# Sensor_Gabung.net
KiCad netlist of a schematic drawn in EAGLE
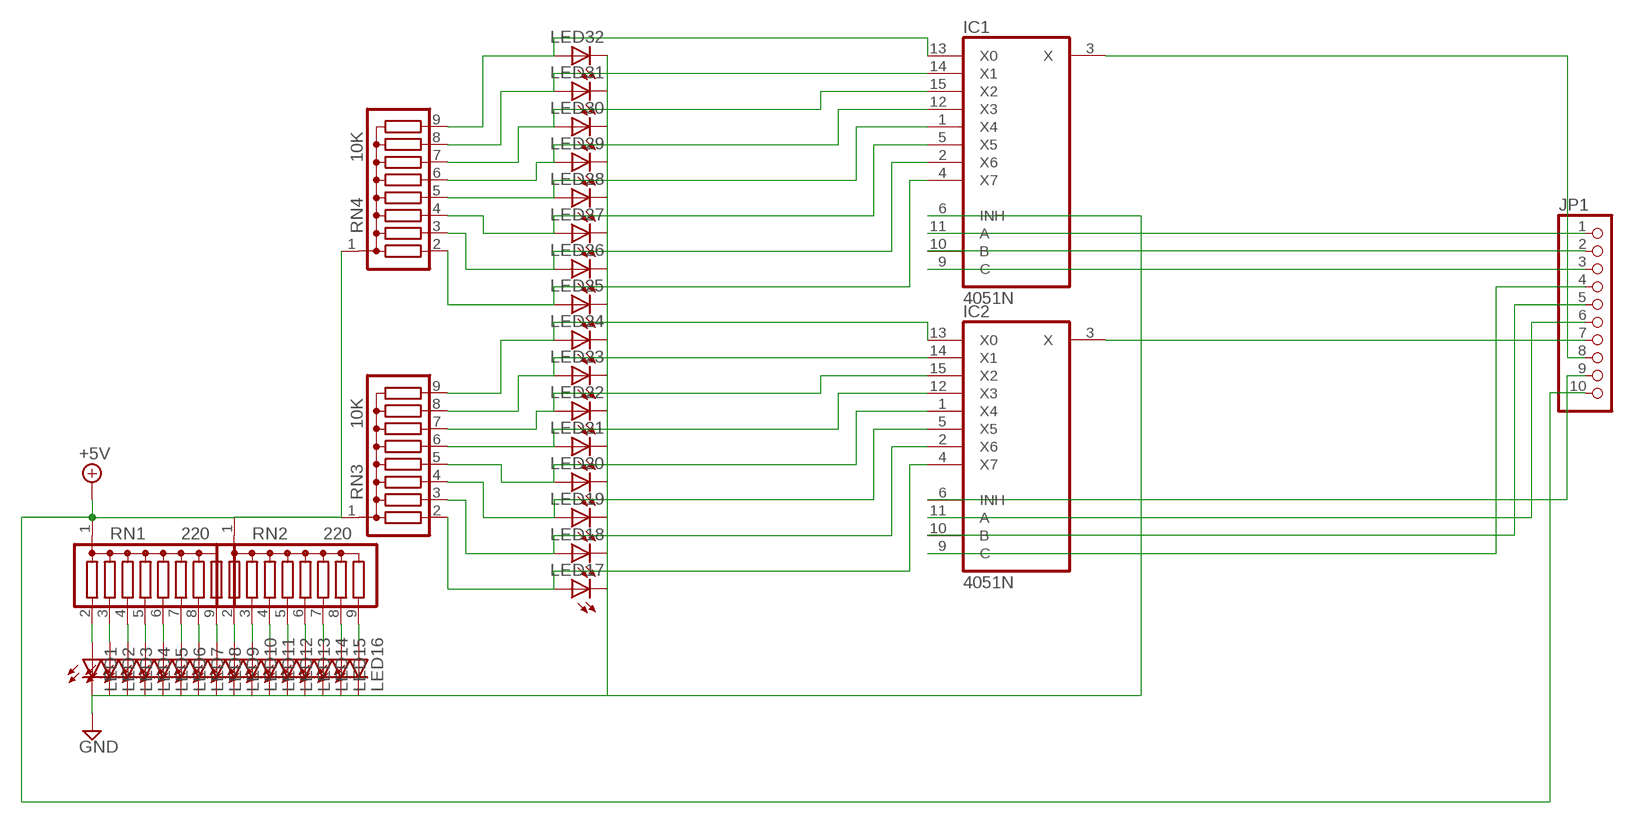
[diagram p0: schematic, sheet 1]
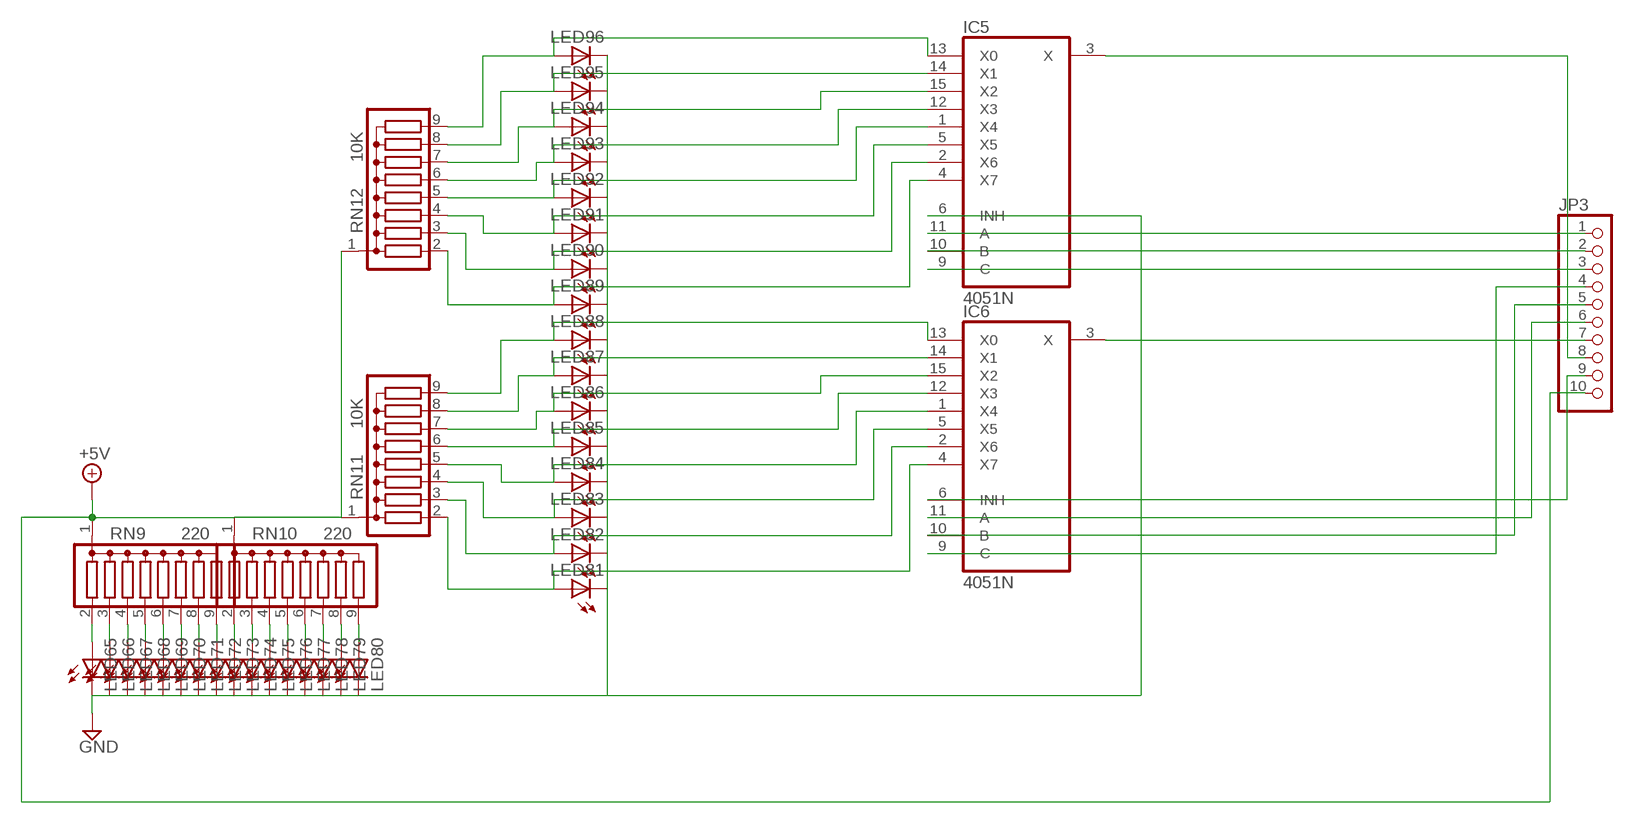
[diagram p1: schematic, sheet 2]
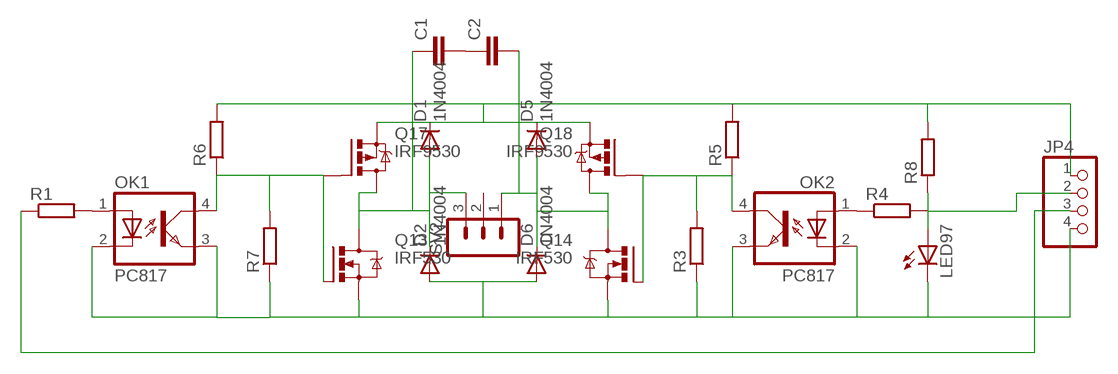
[diagram p2: schematic, sheet 3]
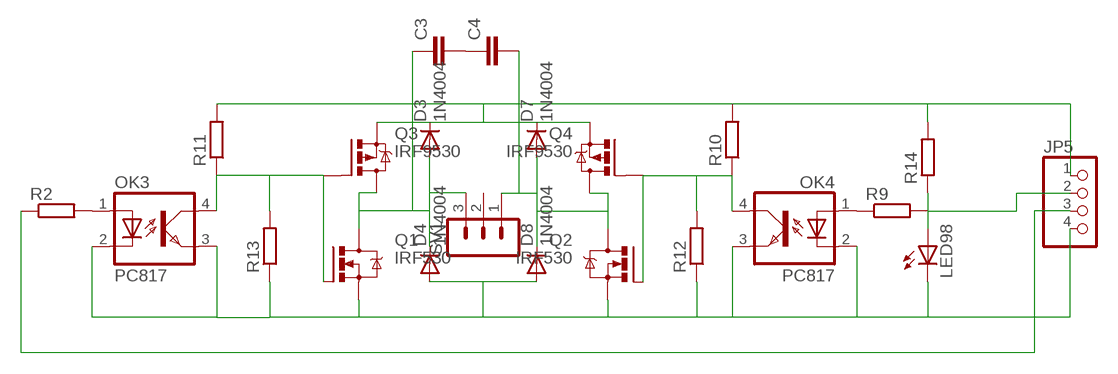
[diagram p3: schematic, sheet 4]
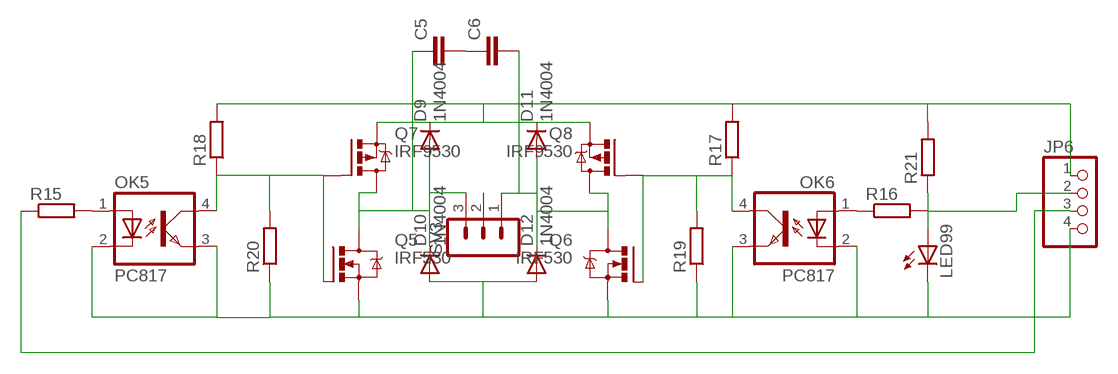
[diagram p4: schematic, sheet 5]
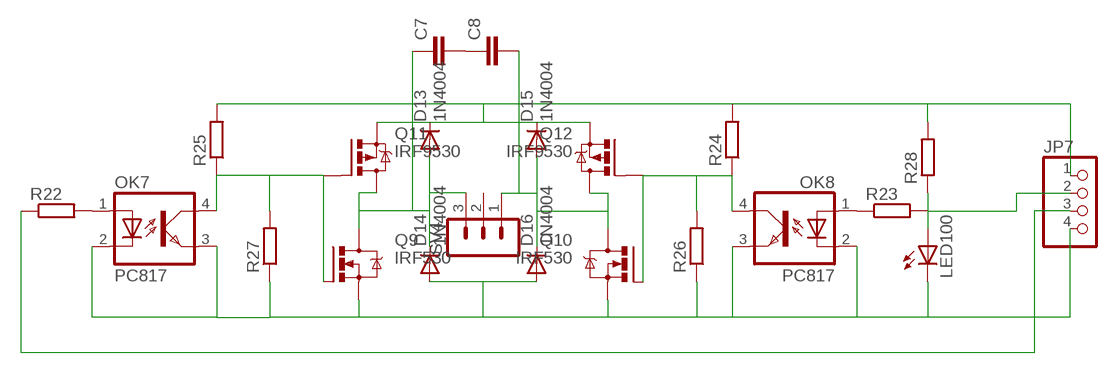
[diagram p5: schematic, sheet 6]
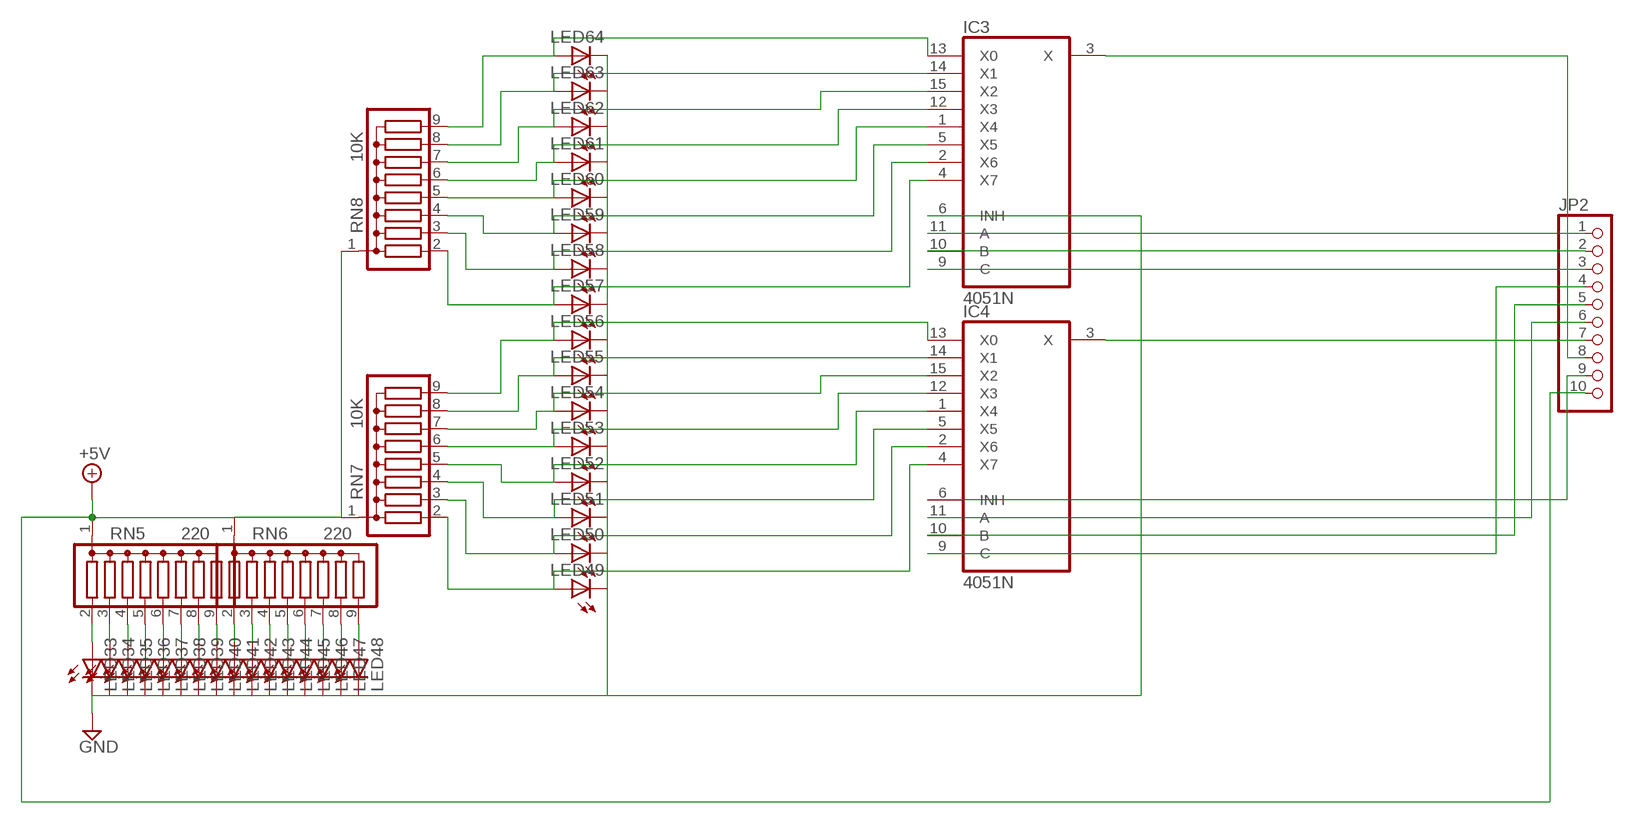
[diagram p6: schematic, sheet 7]
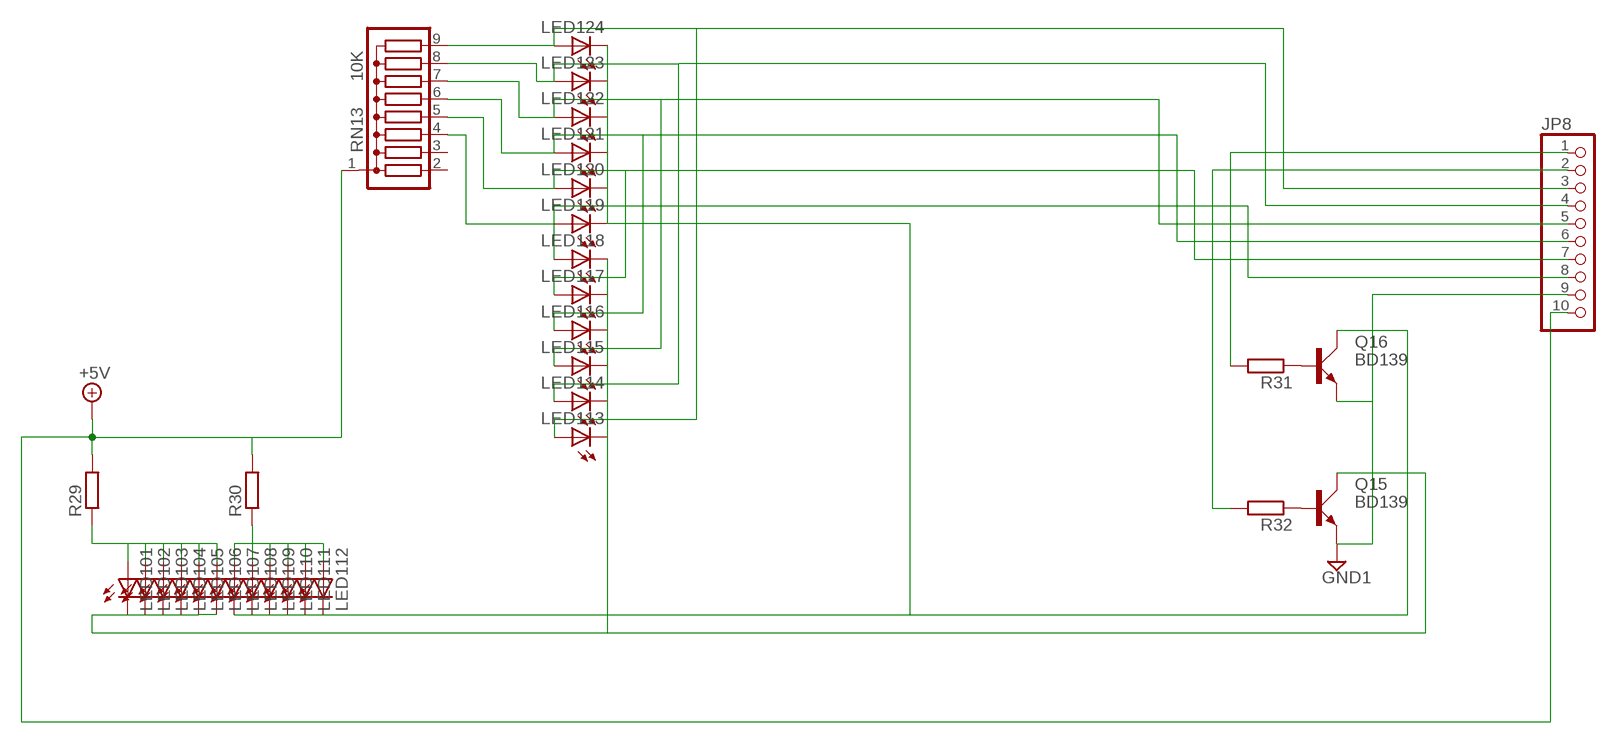
[diagram p7: schematic, sheet 8]
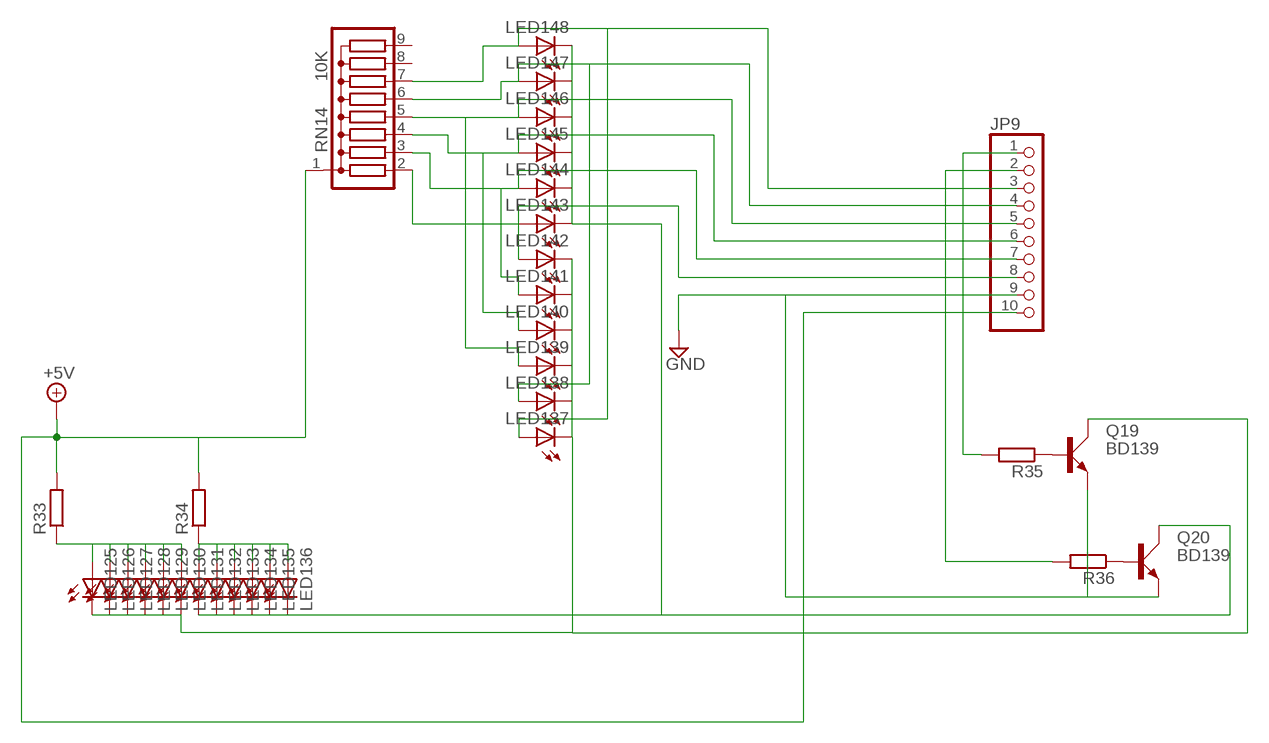
[diagram p8: schematic, sheet 9]

(export (version "E")
  (design (tool "Eeschema 10.0.6"))
  (components
    (comp (ref "JP9")
      (value "PINHD-1X10")
      (footprint "eagle-import:1X10")
      (libsource (lib "eagle-import") (part "PINHD-1X10"))
    )
    (comp (ref "LED125")
      (value "LED3MM")
      (footprint "eagle-import:LED3MM")
      (libsource (lib "eagle-import") (part "LED3MM"))
    )
    (comp (ref "LED126")
      (value "LED3MM")
      (footprint "eagle-import:LED3MM")
      (libsource (lib "eagle-import") (part "LED3MM"))
    )
    (comp (ref "LED127")
      (value "LED3MM")
      (footprint "eagle-import:LED3MM")
      (libsource (lib "eagle-import") (part "LED3MM"))
    )
    (comp (ref "LED128")
      (value "LED3MM")
      (footprint "eagle-import:LED3MM")
      (libsource (lib "eagle-import") (part "LED3MM"))
    )
    (comp (ref "LED129")
      (value "LED3MM")
      (footprint "eagle-import:LED3MM")
      (libsource (lib "eagle-import") (part "LED3MM"))
    )
    (comp (ref "LED130")
      (value "LED3MM")
      (footprint "eagle-import:LED3MM")
      (libsource (lib "eagle-import") (part "LED3MM"))
    )
    (comp (ref "LED131")
      (value "LED3MM")
      (footprint "eagle-import:LED3MM")
      (libsource (lib "eagle-import") (part "LED3MM"))
    )
    (comp (ref "LED132")
      (value "LED3MM")
      (footprint "eagle-import:LED3MM")
      (libsource (lib "eagle-import") (part "LED3MM"))
    )
    (comp (ref "LED133")
      (value "LED3MM")
      (footprint "eagle-import:LED3MM")
      (libsource (lib "eagle-import") (part "LED3MM"))
    )
    (comp (ref "LED134")
      (value "LED3MM")
      (footprint "eagle-import:LED3MM")
      (libsource (lib "eagle-import") (part "LED3MM"))
    )
    (comp (ref "LED135")
      (value "LED3MM")
      (footprint "eagle-import:LED3MM")
      (libsource (lib "eagle-import") (part "LED3MM"))
    )
    (comp (ref "LED136")
      (value "LED3MM")
      (footprint "eagle-import:LED3MM")
      (libsource (lib "eagle-import") (part "LED3MM"))
    )
    (comp (ref "LED137")
      (value "LED3MM")
      (footprint "eagle-import:LED3MM")
      (libsource (lib "eagle-import") (part "LED3MM"))
    )
    (comp (ref "LED138")
      (value "LED3MM")
      (footprint "eagle-import:LED3MM")
      (libsource (lib "eagle-import") (part "LED3MM"))
    )
    (comp (ref "LED139")
      (value "LED3MM")
      (footprint "eagle-import:LED3MM")
      (libsource (lib "eagle-import") (part "LED3MM"))
    )
    (comp (ref "LED140")
      (value "LED3MM")
      (footprint "eagle-import:LED3MM")
      (libsource (lib "eagle-import") (part "LED3MM"))
    )
    (comp (ref "LED141")
      (value "LED3MM")
      (footprint "eagle-import:LED3MM")
      (libsource (lib "eagle-import") (part "LED3MM"))
    )
    (comp (ref "LED142")
      (value "LED3MM")
      (footprint "eagle-import:LED3MM")
      (libsource (lib "eagle-import") (part "LED3MM"))
    )
    (comp (ref "LED143")
      (value "LED3MM")
      (footprint "eagle-import:LED3MM")
      (libsource (lib "eagle-import") (part "LED3MM"))
    )
    (comp (ref "LED144")
      (value "LED3MM")
      (footprint "eagle-import:LED3MM")
      (libsource (lib "eagle-import") (part "LED3MM"))
    )
    (comp (ref "LED145")
      (value "LED3MM")
      (footprint "eagle-import:LED3MM")
      (libsource (lib "eagle-import") (part "LED3MM"))
    )
    (comp (ref "LED146")
      (value "LED3MM")
      (footprint "eagle-import:LED3MM")
      (libsource (lib "eagle-import") (part "LED3MM"))
    )
    (comp (ref "LED147")
      (value "LED3MM")
      (footprint "eagle-import:LED3MM")
      (libsource (lib "eagle-import") (part "LED3MM"))
    )
    (comp (ref "LED148")
      (value "LED3MM")
      (footprint "eagle-import:LED3MM")
      (libsource (lib "eagle-import") (part "LED3MM"))
    )
    (comp (ref "Q19")
      (value "BD139")
      (footprint "eagle-import:TO126AV")
      (libsource (lib "eagle-import") (part "BD139"))
    )
    (comp (ref "Q20")
      (value "BD139")
      (footprint "eagle-import:TO126AV")
      (libsource (lib "eagle-import") (part "BD139"))
    )
    (comp (ref "R33")
      (value "R-EU_0204/7")
      (footprint "eagle-import:0204_7")
      (libsource (lib "eagle-import") (part "R-EU_0204/7"))
    )
    (comp (ref "R34")
      (value "R-EU_0204/7")
      (footprint "eagle-import:0204_7")
      (libsource (lib "eagle-import") (part "R-EU_0204/7"))
    )
    (comp (ref "R35")
      (value "R-EU_0204/7")
      (footprint "eagle-import:0204_7")
      (libsource (lib "eagle-import") (part "R-EU_0204/7"))
    )
    (comp (ref "R36")
      (value "R-EU_0204/7")
      (footprint "eagle-import:0204_7")
      (libsource (lib "eagle-import") (part "R-EU_0204/7"))
    )
    (comp (ref "RN14")
      (value "10K")
      (footprint "eagle-import:SIL9")
      (libsource (lib "eagle-import") (part "G08R"))
    )
    (comp (ref "C5")
      (value "C-EU025-025X050")
      (footprint "eagle-import:C025-025X050")
      (libsource (lib "eagle-import") (part "C-EU025-025X050"))
    )
    (comp (ref "C6")
      (value "C-EU025-025X050")
      (footprint "eagle-import:C025-025X050")
      (libsource (lib "eagle-import") (part "C-EU025-025X050"))
    )
    (comp (ref "D9")
      (value "1N4004")
      (footprint "eagle-import:DO41-10")
      (libsource (lib "eagle-import") (part "1N4004"))
    )
    (comp (ref "D10")
      (value "1N4004")
      (footprint "eagle-import:DO41-10")
      (libsource (lib "eagle-import") (part "1N4004"))
    )
    (comp (ref "D11")
      (value "1N4004")
      (footprint "eagle-import:DO41-10")
      (libsource (lib "eagle-import") (part "1N4004"))
    )
    (comp (ref "D12")
      (value "1N4004")
      (footprint "eagle-import:DO41-10")
      (libsource (lib "eagle-import") (part "1N4004"))
    )
    (comp (ref "JP6")
      (value "PINHD-1X4")
      (footprint "eagle-import:1X04")
      (libsource (lib "eagle-import") (part "PINHD-1X4"))
    )
    (comp (ref "LED99")
      (value "LED3MM")
      (footprint "eagle-import:LED3MM")
      (libsource (lib "eagle-import") (part "LED3MM"))
    )
    (comp (ref "OK5")
      (value "PC817")
      (footprint "eagle-import:DIL04")
      (fields (field (name "MPN") "PC817X4J000F"))
      (libsource (lib "eagle-import") (part "PC817"))
    )
    (comp (ref "OK6")
      (value "PC817")
      (footprint "eagle-import:DIL04")
      (fields (field (name "MPN") "PC817X4J000F"))
      (libsource (lib "eagle-import") (part "PC817"))
    )
    (comp (ref "Q5")
      (value "IRF530")
      (footprint "eagle-import:TO220BV")
      (libsource (lib "eagle-import") (part "IRF530"))
    )
    (comp (ref "Q6")
      (value "IRF530")
      (footprint "eagle-import:TO220BV")
      (libsource (lib "eagle-import") (part "IRF530"))
    )
    (comp (ref "Q7")
      (value "IRF9530")
      (footprint "eagle-import:TO220BV")
      (libsource (lib "eagle-import") (part "IRF9530"))
    )
    (comp (ref "Q8")
      (value "IRF9530")
      (footprint "eagle-import:TO220BV")
      (libsource (lib "eagle-import") (part "IRF9530"))
    )
    (comp (ref "R15")
      (value "R-EU_0207/10")
      (footprint "eagle-import:0207_10")
      (libsource (lib "eagle-import") (part "R-EU_0207/10"))
    )
    (comp (ref "R16")
      (value "R-EU_0207/10")
      (footprint "eagle-import:0207_10")
      (libsource (lib "eagle-import") (part "R-EU_0207/10"))
    )
    (comp (ref "R17")
      (value "R-EU_0207/10")
      (footprint "eagle-import:0207_10")
      (libsource (lib "eagle-import") (part "R-EU_0207/10"))
    )
    (comp (ref "R18")
      (value "R-EU_0207/10")
      (footprint "eagle-import:0207_10")
      (libsource (lib "eagle-import") (part "R-EU_0207/10"))
    )
    (comp (ref "R19")
      (value "R-EU_0204/7")
      (footprint "eagle-import:0204_7")
      (libsource (lib "eagle-import") (part "R-EU_0204/7"))
    )
    (comp (ref "R20")
      (value "R-EU_0204/7")
      (footprint "eagle-import:0204_7")
      (libsource (lib "eagle-import") (part "R-EU_0204/7"))
    )
    (comp (ref "R21")
      (value "R-EU_0207/10")
      (footprint "eagle-import:0207_10")
      (libsource (lib "eagle-import") (part "R-EU_0207/10"))
    )
    (comp (ref "SV3")
      (value "MA03-1")
      (footprint "eagle-import:MA03-1")
      (libsource (lib "eagle-import") (part "MA03-1"))
    )
    (comp (ref "C1")
      (value "C-EU025-025X050")
      (footprint "eagle-import:C025-025X050")
      (libsource (lib "eagle-import") (part "C-EU025-025X050"))
    )
    (comp (ref "C2")
      (value "C-EU025-025X050")
      (footprint "eagle-import:C025-025X050")
      (libsource (lib "eagle-import") (part "C-EU025-025X050"))
    )
    (comp (ref "D1")
      (value "1N4004")
      (footprint "eagle-import:DO41-10")
      (libsource (lib "eagle-import") (part "1N4004"))
    )
    (comp (ref "D2")
      (value "1N4004")
      (footprint "eagle-import:DO41-10")
      (libsource (lib "eagle-import") (part "1N4004"))
    )
    (comp (ref "D5")
      (value "1N4004")
      (footprint "eagle-import:DO41-10")
      (libsource (lib "eagle-import") (part "1N4004"))
    )
    (comp (ref "D6")
      (value "1N4004")
      (footprint "eagle-import:DO41-10")
      (libsource (lib "eagle-import") (part "1N4004"))
    )
    (comp (ref "JP4")
      (value "PINHD-1X4")
      (footprint "eagle-import:1X04")
      (libsource (lib "eagle-import") (part "PINHD-1X4"))
    )
    (comp (ref "LED97")
      (value "LED3MM")
      (footprint "eagle-import:LED3MM")
      (libsource (lib "eagle-import") (part "LED3MM"))
    )
    (comp (ref "OK1")
      (value "PC817")
      (footprint "eagle-import:DIL04")
      (fields (field (name "MPN") "PC817X4J000F"))
      (libsource (lib "eagle-import") (part "PC817"))
    )
    (comp (ref "OK2")
      (value "PC817")
      (footprint "eagle-import:DIL04")
      (fields (field (name "MPN") "PC817X4J000F"))
      (libsource (lib "eagle-import") (part "PC817"))
    )
    (comp (ref "Q13")
      (value "IRF530")
      (footprint "eagle-import:TO220BV")
      (libsource (lib "eagle-import") (part "IRF530"))
    )
    (comp (ref "Q14")
      (value "IRF530")
      (footprint "eagle-import:TO220BV")
      (libsource (lib "eagle-import") (part "IRF530"))
    )
    (comp (ref "Q17")
      (value "IRF9530")
      (footprint "eagle-import:TO220BV")
      (libsource (lib "eagle-import") (part "IRF9530"))
    )
    (comp (ref "Q18")
      (value "IRF9530")
      (footprint "eagle-import:TO220BV")
      (libsource (lib "eagle-import") (part "IRF9530"))
    )
    (comp (ref "R1")
      (value "R-EU_0207/10")
      (footprint "eagle-import:0207_10")
      (libsource (lib "eagle-import") (part "R-EU_0207/10"))
    )
    (comp (ref "R3")
      (value "R-EU_0204/7")
      (footprint "eagle-import:0204_7")
      (libsource (lib "eagle-import") (part "R-EU_0204/7"))
    )
    (comp (ref "R4")
      (value "R-EU_0207/10")
      (footprint "eagle-import:0207_10")
      (libsource (lib "eagle-import") (part "R-EU_0207/10"))
    )
    (comp (ref "R5")
      (value "R-EU_0207/10")
      (footprint "eagle-import:0207_10")
      (libsource (lib "eagle-import") (part "R-EU_0207/10"))
    )
    (comp (ref "R6")
      (value "R-EU_0207/10")
      (footprint "eagle-import:0207_10")
      (libsource (lib "eagle-import") (part "R-EU_0207/10"))
    )
    (comp (ref "R7")
      (value "R-EU_0204/7")
      (footprint "eagle-import:0204_7")
      (libsource (lib "eagle-import") (part "R-EU_0204/7"))
    )
    (comp (ref "R8")
      (value "R-EU_0207/10")
      (footprint "eagle-import:0207_10")
      (libsource (lib "eagle-import") (part "R-EU_0207/10"))
    )
    (comp (ref "SV2")
      (value "MA03-1")
      (footprint "eagle-import:MA03-1")
      (libsource (lib "eagle-import") (part "MA03-1"))
    )
    (comp (ref "C3")
      (value "C-EU025-025X050")
      (footprint "eagle-import:C025-025X050")
      (libsource (lib "eagle-import") (part "C-EU025-025X050"))
    )
    (comp (ref "C4")
      (value "C-EU025-025X050")
      (footprint "eagle-import:C025-025X050")
      (libsource (lib "eagle-import") (part "C-EU025-025X050"))
    )
    (comp (ref "D3")
      (value "1N4004")
      (footprint "eagle-import:DO41-10")
      (libsource (lib "eagle-import") (part "1N4004"))
    )
    (comp (ref "D4")
      (value "1N4004")
      (footprint "eagle-import:DO41-10")
      (libsource (lib "eagle-import") (part "1N4004"))
    )
    (comp (ref "D7")
      (value "1N4004")
      (footprint "eagle-import:DO41-10")
      (libsource (lib "eagle-import") (part "1N4004"))
    )
    (comp (ref "D8")
      (value "1N4004")
      (footprint "eagle-import:DO41-10")
      (libsource (lib "eagle-import") (part "1N4004"))
    )
    (comp (ref "JP5")
      (value "PINHD-1X4")
      (footprint "eagle-import:1X04")
      (libsource (lib "eagle-import") (part "PINHD-1X4"))
    )
    (comp (ref "LED98")
      (value "LED3MM")
      (footprint "eagle-import:LED3MM")
      (libsource (lib "eagle-import") (part "LED3MM"))
    )
    (comp (ref "OK3")
      (value "PC817")
      (footprint "eagle-import:DIL04")
      (fields (field (name "MPN") "PC817X4J000F"))
      (libsource (lib "eagle-import") (part "PC817"))
    )
    (comp (ref "OK4")
      (value "PC817")
      (footprint "eagle-import:DIL04")
      (fields (field (name "MPN") "PC817X4J000F"))
      (libsource (lib "eagle-import") (part "PC817"))
    )
    (comp (ref "Q1")
      (value "IRF530")
      (footprint "eagle-import:TO220BV")
      (libsource (lib "eagle-import") (part "IRF530"))
    )
    (comp (ref "Q2")
      (value "IRF530")
      (footprint "eagle-import:TO220BV")
      (libsource (lib "eagle-import") (part "IRF530"))
    )
    (comp (ref "Q3")
      (value "IRF9530")
      (footprint "eagle-import:TO220BV")
      (libsource (lib "eagle-import") (part "IRF9530"))
    )
    (comp (ref "Q4")
      (value "IRF9530")
      (footprint "eagle-import:TO220BV")
      (libsource (lib "eagle-import") (part "IRF9530"))
    )
    (comp (ref "R2")
      (value "R-EU_0207/10")
      (footprint "eagle-import:0207_10")
      (libsource (lib "eagle-import") (part "R-EU_0207/10"))
    )
    (comp (ref "R9")
      (value "R-EU_0207/10")
      (footprint "eagle-import:0207_10")
      (libsource (lib "eagle-import") (part "R-EU_0207/10"))
    )
    (comp (ref "R10")
      (value "R-EU_0207/10")
      (footprint "eagle-import:0207_10")
      (libsource (lib "eagle-import") (part "R-EU_0207/10"))
    )
    (comp (ref "R11")
      (value "R-EU_0207/10")
      (footprint "eagle-import:0207_10")
      (libsource (lib "eagle-import") (part "R-EU_0207/10"))
    )
    (comp (ref "R12")
      (value "R-EU_0204/7")
      (footprint "eagle-import:0204_7")
      (libsource (lib "eagle-import") (part "R-EU_0204/7"))
    )
    (comp (ref "R13")
      (value "R-EU_0204/7")
      (footprint "eagle-import:0204_7")
      (libsource (lib "eagle-import") (part "R-EU_0204/7"))
    )
    (comp (ref "R14")
      (value "R-EU_0207/10")
      (footprint "eagle-import:0207_10")
      (libsource (lib "eagle-import") (part "R-EU_0207/10"))
    )
    (comp (ref "SV1")
      (value "MA03-1")
      (footprint "eagle-import:MA03-1")
      (libsource (lib "eagle-import") (part "MA03-1"))
    )
    (comp (ref "JP8")
      (value "PINHD-1X10")
      (footprint "eagle-import:1X10")
      (libsource (lib "eagle-import") (part "PINHD-1X10"))
    )
    (comp (ref "LED101")
      (value "LED3MM")
      (footprint "eagle-import:LED3MM")
      (libsource (lib "eagle-import") (part "LED3MM"))
    )
    (comp (ref "LED102")
      (value "LED3MM")
      (footprint "eagle-import:LED3MM")
      (libsource (lib "eagle-import") (part "LED3MM"))
    )
    (comp (ref "LED103")
      (value "LED3MM")
      (footprint "eagle-import:LED3MM")
      (libsource (lib "eagle-import") (part "LED3MM"))
    )
    (comp (ref "LED104")
      (value "LED3MM")
      (footprint "eagle-import:LED3MM")
      (libsource (lib "eagle-import") (part "LED3MM"))
    )
    (comp (ref "LED105")
      (value "LED3MM")
      (footprint "eagle-import:LED3MM")
      (libsource (lib "eagle-import") (part "LED3MM"))
    )
    (comp (ref "LED106")
      (value "LED3MM")
      (footprint "eagle-import:LED3MM")
      (libsource (lib "eagle-import") (part "LED3MM"))
    )
    (comp (ref "LED107")
      (value "LED3MM")
      (footprint "eagle-import:LED3MM")
      (libsource (lib "eagle-import") (part "LED3MM"))
    )
    (comp (ref "LED108")
      (value "LED3MM")
      (footprint "eagle-import:LED3MM")
      (libsource (lib "eagle-import") (part "LED3MM"))
    )
    (comp (ref "LED109")
      (value "LED3MM")
      (footprint "eagle-import:LED3MM")
      (libsource (lib "eagle-import") (part "LED3MM"))
    )
    (comp (ref "LED110")
      (value "LED3MM")
      (footprint "eagle-import:LED3MM")
      (libsource (lib "eagle-import") (part "LED3MM"))
    )
    (comp (ref "LED111")
      (value "LED3MM")
      (footprint "eagle-import:LED3MM")
      (libsource (lib "eagle-import") (part "LED3MM"))
    )
    (comp (ref "LED112")
      (value "LED3MM")
      (footprint "eagle-import:LED3MM")
      (libsource (lib "eagle-import") (part "LED3MM"))
    )
    (comp (ref "LED113")
      (value "LED3MM")
      (footprint "eagle-import:LED3MM")
      (libsource (lib "eagle-import") (part "LED3MM"))
    )
    (comp (ref "LED114")
      (value "LED3MM")
      (footprint "eagle-import:LED3MM")
      (libsource (lib "eagle-import") (part "LED3MM"))
    )
    (comp (ref "LED115")
      (value "LED3MM")
      (footprint "eagle-import:LED3MM")
      (libsource (lib "eagle-import") (part "LED3MM"))
    )
    (comp (ref "LED116")
      (value "LED3MM")
      (footprint "eagle-import:LED3MM")
      (libsource (lib "eagle-import") (part "LED3MM"))
    )
    (comp (ref "LED117")
      (value "LED3MM")
      (footprint "eagle-import:LED3MM")
      (libsource (lib "eagle-import") (part "LED3MM"))
    )
    (comp (ref "LED118")
      (value "LED3MM")
      (footprint "eagle-import:LED3MM")
      (libsource (lib "eagle-import") (part "LED3MM"))
    )
    (comp (ref "LED119")
      (value "LED3MM")
      (footprint "eagle-import:LED3MM")
      (libsource (lib "eagle-import") (part "LED3MM"))
    )
    (comp (ref "LED120")
      (value "LED3MM")
      (footprint "eagle-import:LED3MM")
      (libsource (lib "eagle-import") (part "LED3MM"))
    )
    (comp (ref "LED121")
      (value "LED3MM")
      (footprint "eagle-import:LED3MM")
      (libsource (lib "eagle-import") (part "LED3MM"))
    )
    (comp (ref "LED122")
      (value "LED3MM")
      (footprint "eagle-import:LED3MM")
      (libsource (lib "eagle-import") (part "LED3MM"))
    )
    (comp (ref "LED123")
      (value "LED3MM")
      (footprint "eagle-import:LED3MM")
      (libsource (lib "eagle-import") (part "LED3MM"))
    )
    (comp (ref "LED124")
      (value "LED3MM")
      (footprint "eagle-import:LED3MM")
      (libsource (lib "eagle-import") (part "LED3MM"))
    )
    (comp (ref "Q15")
      (value "BD139")
      (footprint "eagle-import:TO126AV")
      (libsource (lib "eagle-import") (part "BD139"))
    )
    (comp (ref "Q16")
      (value "BD139")
      (footprint "eagle-import:TO126AV")
      (libsource (lib "eagle-import") (part "BD139"))
    )
    (comp (ref "R29")
      (value "R-EU_0207/10")
      (footprint "eagle-import:0207_10")
      (libsource (lib "eagle-import") (part "R-EU_0207/10"))
    )
    (comp (ref "R30")
      (value "R-EU_0207/10")
      (footprint "eagle-import:0207_10")
      (libsource (lib "eagle-import") (part "R-EU_0207/10"))
    )
    (comp (ref "R31")
      (value "R-EU_0207/10")
      (footprint "eagle-import:0207_10")
      (libsource (lib "eagle-import") (part "R-EU_0207/10"))
    )
    (comp (ref "R32")
      (value "R-EU_0207/10")
      (footprint "eagle-import:0207_10")
      (libsource (lib "eagle-import") (part "R-EU_0207/10"))
    )
    (comp (ref "RN13")
      (value "10K")
      (footprint "eagle-import:SIL9")
      (libsource (lib "eagle-import") (part "G08R"))
    )
    (comp (ref "C7")
      (value "C-EU025-025X050")
      (footprint "eagle-import:C025-025X050")
      (libsource (lib "eagle-import") (part "C-EU025-025X050"))
    )
    (comp (ref "C8")
      (value "C-EU025-025X050")
      (footprint "eagle-import:C025-025X050")
      (libsource (lib "eagle-import") (part "C-EU025-025X050"))
    )
    (comp (ref "D13")
      (value "1N4004")
      (footprint "eagle-import:DO41-10")
      (libsource (lib "eagle-import") (part "1N4004"))
    )
    (comp (ref "D14")
      (value "1N4004")
      (footprint "eagle-import:DO41-10")
      (libsource (lib "eagle-import") (part "1N4004"))
    )
    (comp (ref "D15")
      (value "1N4004")
      (footprint "eagle-import:DO41-10")
      (libsource (lib "eagle-import") (part "1N4004"))
    )
    (comp (ref "D16")
      (value "1N4004")
      (footprint "eagle-import:DO41-10")
      (libsource (lib "eagle-import") (part "1N4004"))
    )
    (comp (ref "JP7")
      (value "PINHD-1X4")
      (footprint "eagle-import:1X04")
      (libsource (lib "eagle-import") (part "PINHD-1X4"))
    )
    (comp (ref "LED100")
      (value "LED3MM")
      (footprint "eagle-import:LED3MM")
      (libsource (lib "eagle-import") (part "LED3MM"))
    )
    (comp (ref "OK7")
      (value "PC817")
      (footprint "eagle-import:DIL04")
      (fields (field (name "MPN") "PC817X4J000F"))
      (libsource (lib "eagle-import") (part "PC817"))
    )
    (comp (ref "OK8")
      (value "PC817")
      (footprint "eagle-import:DIL04")
      (fields (field (name "MPN") "PC817X4J000F"))
      (libsource (lib "eagle-import") (part "PC817"))
    )
    (comp (ref "Q9")
      (value "IRF530")
      (footprint "eagle-import:TO220BV")
      (libsource (lib "eagle-import") (part "IRF530"))
    )
    (comp (ref "Q10")
      (value "IRF530")
      (footprint "eagle-import:TO220BV")
      (libsource (lib "eagle-import") (part "IRF530"))
    )
    (comp (ref "Q11")
      (value "IRF9530")
      (footprint "eagle-import:TO220BV")
      (libsource (lib "eagle-import") (part "IRF9530"))
    )
    (comp (ref "Q12")
      (value "IRF9530")
      (footprint "eagle-import:TO220BV")
      (libsource (lib "eagle-import") (part "IRF9530"))
    )
    (comp (ref "R22")
      (value "R-EU_0207/10")
      (footprint "eagle-import:0207_10")
      (libsource (lib "eagle-import") (part "R-EU_0207/10"))
    )
    (comp (ref "R23")
      (value "R-EU_0207/10")
      (footprint "eagle-import:0207_10")
      (libsource (lib "eagle-import") (part "R-EU_0207/10"))
    )
    (comp (ref "R24")
      (value "R-EU_0207/10")
      (footprint "eagle-import:0207_10")
      (libsource (lib "eagle-import") (part "R-EU_0207/10"))
    )
    (comp (ref "R25")
      (value "R-EU_0207/10")
      (footprint "eagle-import:0207_10")
      (libsource (lib "eagle-import") (part "R-EU_0207/10"))
    )
    (comp (ref "R26")
      (value "R-EU_0204/7")
      (footprint "eagle-import:0204_7")
      (libsource (lib "eagle-import") (part "R-EU_0204/7"))
    )
    (comp (ref "R27")
      (value "R-EU_0204/7")
      (footprint "eagle-import:0204_7")
      (libsource (lib "eagle-import") (part "R-EU_0204/7"))
    )
    (comp (ref "R28")
      (value "R-EU_0207/10")
      (footprint "eagle-import:0207_10")
      (libsource (lib "eagle-import") (part "R-EU_0207/10"))
    )
    (comp (ref "SV4")
      (value "MA03-1")
      (footprint "eagle-import:MA03-1")
      (libsource (lib "eagle-import") (part "MA03-1"))
    )
    (comp (ref "IC3")
      (value "4051N")
      (footprint "eagle-import:DIL16")
      (libsource (lib "eagle-import") (part "4051N"))
    )
    (comp (ref "IC4")
      (value "4051N")
      (footprint "eagle-import:DIL16")
      (libsource (lib "eagle-import") (part "4051N"))
    )
    (comp (ref "JP2")
      (value "PINHD-1X10")
      (footprint "eagle-import:1X10")
      (libsource (lib "eagle-import") (part "PINHD-1X10"))
    )
    (comp (ref "LED33")
      (value "LED3MM")
      (footprint "eagle-import:LED3MM")
      (libsource (lib "eagle-import") (part "LED3MM"))
    )
    (comp (ref "LED34")
      (value "LED3MM")
      (footprint "eagle-import:LED3MM")
      (libsource (lib "eagle-import") (part "LED3MM"))
    )
    (comp (ref "LED35")
      (value "LED3MM")
      (footprint "eagle-import:LED3MM")
      (libsource (lib "eagle-import") (part "LED3MM"))
    )
    (comp (ref "LED36")
      (value "LED3MM")
      (footprint "eagle-import:LED3MM")
      (libsource (lib "eagle-import") (part "LED3MM"))
    )
    (comp (ref "LED37")
      (value "LED3MM")
      (footprint "eagle-import:LED3MM")
      (libsource (lib "eagle-import") (part "LED3MM"))
    )
    (comp (ref "LED38")
      (value "LED3MM")
      (footprint "eagle-import:LED3MM")
      (libsource (lib "eagle-import") (part "LED3MM"))
    )
    (comp (ref "LED39")
      (value "LED3MM")
      (footprint "eagle-import:LED3MM")
      (libsource (lib "eagle-import") (part "LED3MM"))
    )
    (comp (ref "LED40")
      (value "LED3MM")
      (footprint "eagle-import:LED3MM")
      (libsource (lib "eagle-import") (part "LED3MM"))
    )
    (comp (ref "LED41")
      (value "LED3MM")
      (footprint "eagle-import:LED3MM")
      (libsource (lib "eagle-import") (part "LED3MM"))
    )
    (comp (ref "LED42")
      (value "LED3MM")
      (footprint "eagle-import:LED3MM")
      (libsource (lib "eagle-import") (part "LED3MM"))
    )
    (comp (ref "LED43")
      (value "LED3MM")
      (footprint "eagle-import:LED3MM")
      (libsource (lib "eagle-import") (part "LED3MM"))
    )
    (comp (ref "LED44")
      (value "LED3MM")
      (footprint "eagle-import:LED3MM")
      (libsource (lib "eagle-import") (part "LED3MM"))
    )
    (comp (ref "LED45")
      (value "LED3MM")
      (footprint "eagle-import:LED3MM")
      (libsource (lib "eagle-import") (part "LED3MM"))
    )
    (comp (ref "LED46")
      (value "LED3MM")
      (footprint "eagle-import:LED3MM")
      (libsource (lib "eagle-import") (part "LED3MM"))
    )
    (comp (ref "LED47")
      (value "LED3MM")
      (footprint "eagle-import:LED3MM")
      (libsource (lib "eagle-import") (part "LED3MM"))
    )
    (comp (ref "LED48")
      (value "LED3MM")
      (footprint "eagle-import:LED3MM")
      (libsource (lib "eagle-import") (part "LED3MM"))
    )
    (comp (ref "LED49")
      (value "LED3MM")
      (footprint "eagle-import:LED3MM")
      (libsource (lib "eagle-import") (part "LED3MM"))
    )
    (comp (ref "LED50")
      (value "LED3MM")
      (footprint "eagle-import:LED3MM")
      (libsource (lib "eagle-import") (part "LED3MM"))
    )
    (comp (ref "LED51")
      (value "LED3MM")
      (footprint "eagle-import:LED3MM")
      (libsource (lib "eagle-import") (part "LED3MM"))
    )
    (comp (ref "LED52")
      (value "LED3MM")
      (footprint "eagle-import:LED3MM")
      (libsource (lib "eagle-import") (part "LED3MM"))
    )
    (comp (ref "LED53")
      (value "LED3MM")
      (footprint "eagle-import:LED3MM")
      (libsource (lib "eagle-import") (part "LED3MM"))
    )
    (comp (ref "LED54")
      (value "LED3MM")
      (footprint "eagle-import:LED3MM")
      (libsource (lib "eagle-import") (part "LED3MM"))
    )
    (comp (ref "LED55")
      (value "LED3MM")
      (footprint "eagle-import:LED3MM")
      (libsource (lib "eagle-import") (part "LED3MM"))
    )
    (comp (ref "LED56")
      (value "LED3MM")
      (footprint "eagle-import:LED3MM")
      (libsource (lib "eagle-import") (part "LED3MM"))
    )
    (comp (ref "LED57")
      (value "LED3MM")
      (footprint "eagle-import:LED3MM")
      (libsource (lib "eagle-import") (part "LED3MM"))
    )
    (comp (ref "LED58")
      (value "LED3MM")
      (footprint "eagle-import:LED3MM")
      (libsource (lib "eagle-import") (part "LED3MM"))
    )
    (comp (ref "LED59")
      (value "LED3MM")
      (footprint "eagle-import:LED3MM")
      (libsource (lib "eagle-import") (part "LED3MM"))
    )
    (comp (ref "LED60")
      (value "LED3MM")
      (footprint "eagle-import:LED3MM")
      (libsource (lib "eagle-import") (part "LED3MM"))
    )
    (comp (ref "LED61")
      (value "LED3MM")
      (footprint "eagle-import:LED3MM")
      (libsource (lib "eagle-import") (part "LED3MM"))
    )
    (comp (ref "LED62")
      (value "LED3MM")
      (footprint "eagle-import:LED3MM")
      (libsource (lib "eagle-import") (part "LED3MM"))
    )
    (comp (ref "LED63")
      (value "LED3MM")
      (footprint "eagle-import:LED3MM")
      (libsource (lib "eagle-import") (part "LED3MM"))
    )
    (comp (ref "LED64")
      (value "LED3MM")
      (footprint "eagle-import:LED3MM")
      (libsource (lib "eagle-import") (part "LED3MM"))
    )
    (comp (ref "RN5")
      (value "220")
      (footprint "eagle-import:SIL9")
      (libsource (lib "eagle-import") (part "G08R"))
    )
    (comp (ref "RN6")
      (value "220")
      (footprint "eagle-import:SIL9")
      (libsource (lib "eagle-import") (part "G08R"))
    )
    (comp (ref "RN7")
      (value "10K")
      (footprint "eagle-import:SIL9")
      (libsource (lib "eagle-import") (part "G08R"))
    )
    (comp (ref "RN8")
      (value "10K")
      (footprint "eagle-import:SIL9")
      (libsource (lib "eagle-import") (part "G08R"))
    )
    (comp (ref "IC1")
      (value "4051N")
      (footprint "eagle-import:DIL16")
      (libsource (lib "eagle-import") (part "4051N"))
    )
    (comp (ref "IC2")
      (value "4051N")
      (footprint "eagle-import:DIL16")
      (libsource (lib "eagle-import") (part "4051N"))
    )
    (comp (ref "JP1")
      (value "PINHD-1X10")
      (footprint "eagle-import:1X10")
      (libsource (lib "eagle-import") (part "PINHD-1X10"))
    )
    (comp (ref "LED1")
      (value "LED3MM")
      (footprint "eagle-import:LED3MM")
      (libsource (lib "eagle-import") (part "LED3MM"))
    )
    (comp (ref "LED2")
      (value "LED3MM")
      (footprint "eagle-import:LED3MM")
      (libsource (lib "eagle-import") (part "LED3MM"))
    )
    (comp (ref "LED3")
      (value "LED3MM")
      (footprint "eagle-import:LED3MM")
      (libsource (lib "eagle-import") (part "LED3MM"))
    )
    (comp (ref "LED4")
      (value "LED3MM")
      (footprint "eagle-import:LED3MM")
      (libsource (lib "eagle-import") (part "LED3MM"))
    )
    (comp (ref "LED5")
      (value "LED3MM")
      (footprint "eagle-import:LED3MM")
      (libsource (lib "eagle-import") (part "LED3MM"))
    )
    (comp (ref "LED6")
      (value "LED3MM")
      (footprint "eagle-import:LED3MM")
      (libsource (lib "eagle-import") (part "LED3MM"))
    )
    (comp (ref "LED7")
      (value "LED3MM")
      (footprint "eagle-import:LED3MM")
      (libsource (lib "eagle-import") (part "LED3MM"))
    )
    (comp (ref "LED8")
      (value "LED3MM")
      (footprint "eagle-import:LED3MM")
      (libsource (lib "eagle-import") (part "LED3MM"))
    )
    (comp (ref "LED9")
      (value "LED3MM")
      (footprint "eagle-import:LED3MM")
      (libsource (lib "eagle-import") (part "LED3MM"))
    )
    (comp (ref "LED10")
      (value "LED3MM")
      (footprint "eagle-import:LED3MM")
      (libsource (lib "eagle-import") (part "LED3MM"))
    )
    (comp (ref "LED11")
      (value "LED3MM")
      (footprint "eagle-import:LED3MM")
      (libsource (lib "eagle-import") (part "LED3MM"))
    )
    (comp (ref "LED12")
      (value "LED3MM")
      (footprint "eagle-import:LED3MM")
      (libsource (lib "eagle-import") (part "LED3MM"))
    )
    (comp (ref "LED13")
      (value "LED3MM")
      (footprint "eagle-import:LED3MM")
      (libsource (lib "eagle-import") (part "LED3MM"))
    )
    (comp (ref "LED14")
      (value "LED3MM")
      (footprint "eagle-import:LED3MM")
      (libsource (lib "eagle-import") (part "LED3MM"))
    )
    (comp (ref "LED15")
      (value "LED3MM")
      (footprint "eagle-import:LED3MM")
      (libsource (lib "eagle-import") (part "LED3MM"))
    )
    (comp (ref "LED16")
      (value "LED3MM")
      (footprint "eagle-import:LED3MM")
      (libsource (lib "eagle-import") (part "LED3MM"))
    )
    (comp (ref "LED17")
      (value "LED3MM")
      (footprint "eagle-import:LED3MM")
      (libsource (lib "eagle-import") (part "LED3MM"))
    )
    (comp (ref "LED18")
      (value "LED3MM")
      (footprint "eagle-import:LED3MM")
      (libsource (lib "eagle-import") (part "LED3MM"))
    )
    (comp (ref "LED19")
      (value "LED3MM")
      (footprint "eagle-import:LED3MM")
      (libsource (lib "eagle-import") (part "LED3MM"))
    )
    (comp (ref "LED20")
      (value "LED3MM")
      (footprint "eagle-import:LED3MM")
      (libsource (lib "eagle-import") (part "LED3MM"))
    )
    (comp (ref "LED21")
      (value "LED3MM")
      (footprint "eagle-import:LED3MM")
      (libsource (lib "eagle-import") (part "LED3MM"))
    )
    (comp (ref "LED22")
      (value "LED3MM")
      (footprint "eagle-import:LED3MM")
      (libsource (lib "eagle-import") (part "LED3MM"))
    )
    (comp (ref "LED23")
      (value "LED3MM")
      (footprint "eagle-import:LED3MM")
      (libsource (lib "eagle-import") (part "LED3MM"))
    )
    (comp (ref "LED24")
      (value "LED3MM")
      (footprint "eagle-import:LED3MM")
      (libsource (lib "eagle-import") (part "LED3MM"))
    )
    (comp (ref "LED25")
      (value "LED3MM")
      (footprint "eagle-import:LED3MM")
      (libsource (lib "eagle-import") (part "LED3MM"))
    )
    (comp (ref "LED26")
      (value "LED3MM")
      (footprint "eagle-import:LED3MM")
      (libsource (lib "eagle-import") (part "LED3MM"))
    )
    (comp (ref "LED27")
      (value "LED3MM")
      (footprint "eagle-import:LED3MM")
      (libsource (lib "eagle-import") (part "LED3MM"))
    )
    (comp (ref "LED28")
      (value "LED3MM")
      (footprint "eagle-import:LED3MM")
      (libsource (lib "eagle-import") (part "LED3MM"))
    )
    (comp (ref "LED29")
      (value "LED3MM")
      (footprint "eagle-import:LED3MM")
      (libsource (lib "eagle-import") (part "LED3MM"))
    )
    (comp (ref "LED30")
      (value "LED3MM")
      (footprint "eagle-import:LED3MM")
      (libsource (lib "eagle-import") (part "LED3MM"))
    )
    (comp (ref "LED31")
      (value "LED3MM")
      (footprint "eagle-import:LED3MM")
      (libsource (lib "eagle-import") (part "LED3MM"))
    )
    (comp (ref "LED32")
      (value "LED3MM")
      (footprint "eagle-import:LED3MM")
      (libsource (lib "eagle-import") (part "LED3MM"))
    )
    (comp (ref "RN1")
      (value "220")
      (footprint "eagle-import:SIL9")
      (libsource (lib "eagle-import") (part "G08R"))
    )
    (comp (ref "RN2")
      (value "220")
      (footprint "eagle-import:SIL9")
      (libsource (lib "eagle-import") (part "G08R"))
    )
    (comp (ref "RN3")
      (value "10K")
      (footprint "eagle-import:SIL9")
      (libsource (lib "eagle-import") (part "G08R"))
    )
    (comp (ref "RN4")
      (value "10K")
      (footprint "eagle-import:SIL9")
      (libsource (lib "eagle-import") (part "G08R"))
    )
    (comp (ref "IC5")
      (value "4051N")
      (footprint "eagle-import:DIL16")
      (libsource (lib "eagle-import") (part "4051N"))
    )
    (comp (ref "IC6")
      (value "4051N")
      (footprint "eagle-import:DIL16")
      (libsource (lib "eagle-import") (part "4051N"))
    )
    (comp (ref "JP3")
      (value "PINHD-1X10")
      (footprint "eagle-import:1X10")
      (libsource (lib "eagle-import") (part "PINHD-1X10"))
    )
    (comp (ref "LED65")
      (value "LED3MM")
      (footprint "eagle-import:LED3MM")
      (libsource (lib "eagle-import") (part "LED3MM"))
    )
    (comp (ref "LED66")
      (value "LED3MM")
      (footprint "eagle-import:LED3MM")
      (libsource (lib "eagle-import") (part "LED3MM"))
    )
    (comp (ref "LED67")
      (value "LED3MM")
      (footprint "eagle-import:LED3MM")
      (libsource (lib "eagle-import") (part "LED3MM"))
    )
    (comp (ref "LED68")
      (value "LED3MM")
      (footprint "eagle-import:LED3MM")
      (libsource (lib "eagle-import") (part "LED3MM"))
    )
    (comp (ref "LED69")
      (value "LED3MM")
      (footprint "eagle-import:LED3MM")
      (libsource (lib "eagle-import") (part "LED3MM"))
    )
    (comp (ref "LED70")
      (value "LED3MM")
      (footprint "eagle-import:LED3MM")
      (libsource (lib "eagle-import") (part "LED3MM"))
    )
    (comp (ref "LED71")
      (value "LED3MM")
      (footprint "eagle-import:LED3MM")
      (libsource (lib "eagle-import") (part "LED3MM"))
    )
    (comp (ref "LED72")
      (value "LED3MM")
      (footprint "eagle-import:LED3MM")
      (libsource (lib "eagle-import") (part "LED3MM"))
    )
    (comp (ref "LED73")
      (value "LED3MM")
      (footprint "eagle-import:LED3MM")
      (libsource (lib "eagle-import") (part "LED3MM"))
    )
    (comp (ref "LED74")
      (value "LED3MM")
      (footprint "eagle-import:LED3MM")
      (libsource (lib "eagle-import") (part "LED3MM"))
    )
    (comp (ref "LED75")
      (value "LED3MM")
      (footprint "eagle-import:LED3MM")
      (libsource (lib "eagle-import") (part "LED3MM"))
    )
    (comp (ref "LED76")
      (value "LED3MM")
      (footprint "eagle-import:LED3MM")
      (libsource (lib "eagle-import") (part "LED3MM"))
    )
    (comp (ref "LED77")
      (value "LED3MM")
      (footprint "eagle-import:LED3MM")
      (libsource (lib "eagle-import") (part "LED3MM"))
    )
    (comp (ref "LED78")
      (value "LED3MM")
      (footprint "eagle-import:LED3MM")
      (libsource (lib "eagle-import") (part "LED3MM"))
    )
    (comp (ref "LED79")
      (value "LED3MM")
      (footprint "eagle-import:LED3MM")
      (libsource (lib "eagle-import") (part "LED3MM"))
    )
    (comp (ref "LED80")
      (value "LED3MM")
      (footprint "eagle-import:LED3MM")
      (libsource (lib "eagle-import") (part "LED3MM"))
    )
    (comp (ref "LED81")
      (value "LED3MM")
      (footprint "eagle-import:LED3MM")
      (libsource (lib "eagle-import") (part "LED3MM"))
    )
    (comp (ref "LED82")
      (value "LED3MM")
      (footprint "eagle-import:LED3MM")
      (libsource (lib "eagle-import") (part "LED3MM"))
    )
    (comp (ref "LED83")
      (value "LED3MM")
      (footprint "eagle-import:LED3MM")
      (libsource (lib "eagle-import") (part "LED3MM"))
    )
    (comp (ref "LED84")
      (value "LED3MM")
      (footprint "eagle-import:LED3MM")
      (libsource (lib "eagle-import") (part "LED3MM"))
    )
    (comp (ref "LED85")
      (value "LED3MM")
      (footprint "eagle-import:LED3MM")
      (libsource (lib "eagle-import") (part "LED3MM"))
    )
    (comp (ref "LED86")
      (value "LED3MM")
      (footprint "eagle-import:LED3MM")
      (libsource (lib "eagle-import") (part "LED3MM"))
    )
    (comp (ref "LED87")
      (value "LED3MM")
      (footprint "eagle-import:LED3MM")
      (libsource (lib "eagle-import") (part "LED3MM"))
    )
    (comp (ref "LED88")
      (value "LED3MM")
      (footprint "eagle-import:LED3MM")
      (libsource (lib "eagle-import") (part "LED3MM"))
    )
    (comp (ref "LED89")
      (value "LED3MM")
      (footprint "eagle-import:LED3MM")
      (libsource (lib "eagle-import") (part "LED3MM"))
    )
    (comp (ref "LED90")
      (value "LED3MM")
      (footprint "eagle-import:LED3MM")
      (libsource (lib "eagle-import") (part "LED3MM"))
    )
    (comp (ref "LED91")
      (value "LED3MM")
      (footprint "eagle-import:LED3MM")
      (libsource (lib "eagle-import") (part "LED3MM"))
    )
    (comp (ref "LED92")
      (value "LED3MM")
      (footprint "eagle-import:LED3MM")
      (libsource (lib "eagle-import") (part "LED3MM"))
    )
    (comp (ref "LED93")
      (value "LED3MM")
      (footprint "eagle-import:LED3MM")
      (libsource (lib "eagle-import") (part "LED3MM"))
    )
    (comp (ref "LED94")
      (value "LED3MM")
      (footprint "eagle-import:LED3MM")
      (libsource (lib "eagle-import") (part "LED3MM"))
    )
    (comp (ref "LED95")
      (value "LED3MM")
      (footprint "eagle-import:LED3MM")
      (libsource (lib "eagle-import") (part "LED3MM"))
    )
    (comp (ref "LED96")
      (value "LED3MM")
      (footprint "eagle-import:LED3MM")
      (libsource (lib "eagle-import") (part "LED3MM"))
    )
    (comp (ref "RN9")
      (value "220")
      (footprint "eagle-import:SIL9")
      (libsource (lib "eagle-import") (part "G08R"))
    )
    (comp (ref "RN10")
      (value "220")
      (footprint "eagle-import:SIL9")
      (libsource (lib "eagle-import") (part "G08R"))
    )
    (comp (ref "RN11")
      (value "10K")
      (footprint "eagle-import:SIL9")
      (libsource (lib "eagle-import") (part "G08R"))
    )
    (comp (ref "RN12")
      (value "10K")
      (footprint "eagle-import:SIL9")
      (libsource (lib "eagle-import") (part "G08R"))
    )
  )
  (nets
    (net (code "1") (name "+5V") (class "Default")
      (node (ref "JP1") (pin "10") (pinfunction "10_10") (pintype "passive"))
      (node (ref "JP2") (pin "10") (pinfunction "10_10") (pintype "passive"))
      (node (ref "JP3") (pin "10") (pinfunction "10_10") (pintype "passive"))
      (node (ref "JP8") (pin "10") (pinfunction "10_10") (pintype "passive"))
      (node (ref "JP9") (pin "10") (pinfunction "10_10") (pintype "passive"))
      (node (ref "R29") (pin "2") (pinfunction "2_2") (pintype "passive"))
      (node (ref "R30") (pin "2") (pinfunction "2_2") (pintype "passive"))
      (node (ref "R33") (pin "2") (pinfunction "2_2") (pintype "passive"))
      (node (ref "R34") (pin "2") (pinfunction "2_2") (pintype "passive"))
      (node (ref "RN1") (pin "1") (pinfunction "1_1") (pintype "passive"))
      (node (ref "RN10") (pin "1") (pinfunction "1_1") (pintype "passive"))
      (node (ref "RN11") (pin "1") (pinfunction "1_1") (pintype "passive"))
      (node (ref "RN12") (pin "1") (pinfunction "1_1") (pintype "passive"))
      (node (ref "RN13") (pin "1") (pinfunction "1_1") (pintype "passive"))
      (node (ref "RN14") (pin "1") (pinfunction "1_1") (pintype "passive"))
      (node (ref "RN2") (pin "1") (pinfunction "1_1") (pintype "passive"))
      (node (ref "RN3") (pin "1") (pinfunction "1_1") (pintype "passive"))
      (node (ref "RN4") (pin "1") (pinfunction "1_1") (pintype "passive"))
      (node (ref "RN5") (pin "1") (pinfunction "1_1") (pintype "passive"))
      (node (ref "RN6") (pin "1") (pinfunction "1_1") (pintype "passive"))
      (node (ref "RN7") (pin "1") (pinfunction "1_1") (pintype "passive"))
      (node (ref "RN8") (pin "1") (pinfunction "1_1") (pintype "passive"))
      (node (ref "RN9") (pin "1") (pinfunction "1_1") (pintype "passive"))
    )
    (net (code "2") (name "GND") (class "Default")
      (node (ref "IC1") (pin "6") (pinfunction "INH_6") (pintype "input"))
      (node (ref "IC2") (pin "6") (pinfunction "INH_6") (pintype "input"))
      (node (ref "IC3") (pin "6") (pinfunction "INH_6") (pintype "input"))
      (node (ref "IC4") (pin "6") (pinfunction "INH_6") (pintype "input"))
      (node (ref "IC5") (pin "6") (pinfunction "INH_6") (pintype "input"))
      (node (ref "IC6") (pin "6") (pinfunction "INH_6") (pintype "input"))
      (node (ref "JP1") (pin "9") (pinfunction "9_9") (pintype "passive"))
      (node (ref "JP2") (pin "9") (pinfunction "9_9") (pintype "passive"))
      (node (ref "JP3") (pin "9") (pinfunction "9_9") (pintype "passive"))
      (node (ref "JP9") (pin "9") (pinfunction "9_9") (pintype "passive"))
      (node (ref "LED1") (pin "K") (pinfunction "C_K") (pintype "passive"))
      (node (ref "LED10") (pin "K") (pinfunction "C_K") (pintype "passive"))
      (node (ref "LED11") (pin "K") (pinfunction "C_K") (pintype "passive"))
      (node (ref "LED12") (pin "K") (pinfunction "C_K") (pintype "passive"))
      (node (ref "LED13") (pin "K") (pinfunction "C_K") (pintype "passive"))
      (node (ref "LED14") (pin "K") (pinfunction "C_K") (pintype "passive"))
      (node (ref "LED15") (pin "K") (pinfunction "C_K") (pintype "passive"))
      (node (ref "LED16") (pin "K") (pinfunction "C_K") (pintype "passive"))
      (node (ref "LED17") (pin "K") (pinfunction "C_K") (pintype "passive"))
      (node (ref "LED18") (pin "K") (pinfunction "C_K") (pintype "passive"))
      (node (ref "LED19") (pin "K") (pinfunction "C_K") (pintype "passive"))
      (node (ref "LED2") (pin "K") (pinfunction "C_K") (pintype "passive"))
      (node (ref "LED20") (pin "K") (pinfunction "C_K") (pintype "passive"))
      (node (ref "LED21") (pin "K") (pinfunction "C_K") (pintype "passive"))
      (node (ref "LED22") (pin "K") (pinfunction "C_K") (pintype "passive"))
      (node (ref "LED23") (pin "K") (pinfunction "C_K") (pintype "passive"))
      (node (ref "LED24") (pin "K") (pinfunction "C_K") (pintype "passive"))
      (node (ref "LED25") (pin "K") (pinfunction "C_K") (pintype "passive"))
      (node (ref "LED26") (pin "K") (pinfunction "C_K") (pintype "passive"))
      (node (ref "LED27") (pin "K") (pinfunction "C_K") (pintype "passive"))
      (node (ref "LED28") (pin "K") (pinfunction "C_K") (pintype "passive"))
      (node (ref "LED29") (pin "K") (pinfunction "C_K") (pintype "passive"))
      (node (ref "LED3") (pin "K") (pinfunction "C_K") (pintype "passive"))
      (node (ref "LED30") (pin "K") (pinfunction "C_K") (pintype "passive"))
      (node (ref "LED31") (pin "K") (pinfunction "C_K") (pintype "passive"))
      (node (ref "LED32") (pin "K") (pinfunction "C_K") (pintype "passive"))
      (node (ref "LED33") (pin "K") (pinfunction "C_K") (pintype "passive"))
      (node (ref "LED34") (pin "K") (pinfunction "C_K") (pintype "passive"))
      (node (ref "LED35") (pin "K") (pinfunction "C_K") (pintype "passive"))
      (node (ref "LED36") (pin "K") (pinfunction "C_K") (pintype "passive"))
      (node (ref "LED37") (pin "K") (pinfunction "C_K") (pintype "passive"))
      (node (ref "LED38") (pin "K") (pinfunction "C_K") (pintype "passive"))
      (node (ref "LED39") (pin "K") (pinfunction "C_K") (pintype "passive"))
      (node (ref "LED4") (pin "K") (pinfunction "C_K") (pintype "passive"))
      (node (ref "LED40") (pin "K") (pinfunction "C_K") (pintype "passive"))
      (node (ref "LED41") (pin "K") (pinfunction "C_K") (pintype "passive"))
      (node (ref "LED42") (pin "K") (pinfunction "C_K") (pintype "passive"))
      (node (ref "LED43") (pin "K") (pinfunction "C_K") (pintype "passive"))
      (node (ref "LED44") (pin "K") (pinfunction "C_K") (pintype "passive"))
      (node (ref "LED45") (pin "K") (pinfunction "C_K") (pintype "passive"))
      (node (ref "LED46") (pin "K") (pinfunction "C_K") (pintype "passive"))
      (node (ref "LED47") (pin "K") (pinfunction "C_K") (pintype "passive"))
      (node (ref "LED48") (pin "K") (pinfunction "C_K") (pintype "passive"))
      (node (ref "LED49") (pin "K") (pinfunction "C_K") (pintype "passive"))
      (node (ref "LED5") (pin "K") (pinfunction "C_K") (pintype "passive"))
      (node (ref "LED50") (pin "K") (pinfunction "C_K") (pintype "passive"))
      (node (ref "LED51") (pin "K") (pinfunction "C_K") (pintype "passive"))
      (node (ref "LED52") (pin "K") (pinfunction "C_K") (pintype "passive"))
      (node (ref "LED53") (pin "K") (pinfunction "C_K") (pintype "passive"))
      (node (ref "LED54") (pin "K") (pinfunction "C_K") (pintype "passive"))
      (node (ref "LED55") (pin "K") (pinfunction "C_K") (pintype "passive"))
      (node (ref "LED56") (pin "K") (pinfunction "C_K") (pintype "passive"))
      (node (ref "LED57") (pin "K") (pinfunction "C_K") (pintype "passive"))
      (node (ref "LED58") (pin "K") (pinfunction "C_K") (pintype "passive"))
      (node (ref "LED59") (pin "K") (pinfunction "C_K") (pintype "passive"))
      (node (ref "LED6") (pin "K") (pinfunction "C_K") (pintype "passive"))
      (node (ref "LED60") (pin "K") (pinfunction "C_K") (pintype "passive"))
      (node (ref "LED61") (pin "K") (pinfunction "C_K") (pintype "passive"))
      (node (ref "LED62") (pin "K") (pinfunction "C_K") (pintype "passive"))
      (node (ref "LED63") (pin "K") (pinfunction "C_K") (pintype "passive"))
      (node (ref "LED64") (pin "K") (pinfunction "C_K") (pintype "passive"))
      (node (ref "LED65") (pin "K") (pinfunction "C_K") (pintype "passive"))
      (node (ref "LED66") (pin "K") (pinfunction "C_K") (pintype "passive"))
      (node (ref "LED67") (pin "K") (pinfunction "C_K") (pintype "passive"))
      (node (ref "LED68") (pin "K") (pinfunction "C_K") (pintype "passive"))
      (node (ref "LED69") (pin "K") (pinfunction "C_K") (pintype "passive"))
      (node (ref "LED7") (pin "K") (pinfunction "C_K") (pintype "passive"))
      (node (ref "LED70") (pin "K") (pinfunction "C_K") (pintype "passive"))
      (node (ref "LED71") (pin "K") (pinfunction "C_K") (pintype "passive"))
      (node (ref "LED72") (pin "K") (pinfunction "C_K") (pintype "passive"))
      (node (ref "LED73") (pin "K") (pinfunction "C_K") (pintype "passive"))
      (node (ref "LED74") (pin "K") (pinfunction "C_K") (pintype "passive"))
      (node (ref "LED75") (pin "K") (pinfunction "C_K") (pintype "passive"))
      (node (ref "LED76") (pin "K") (pinfunction "C_K") (pintype "passive"))
      (node (ref "LED77") (pin "K") (pinfunction "C_K") (pintype "passive"))
      (node (ref "LED78") (pin "K") (pinfunction "C_K") (pintype "passive"))
      (node (ref "LED79") (pin "K") (pinfunction "C_K") (pintype "passive"))
      (node (ref "LED8") (pin "K") (pinfunction "C_K") (pintype "passive"))
      (node (ref "LED80") (pin "K") (pinfunction "C_K") (pintype "passive"))
      (node (ref "LED81") (pin "K") (pinfunction "C_K") (pintype "passive"))
      (node (ref "LED82") (pin "K") (pinfunction "C_K") (pintype "passive"))
      (node (ref "LED83") (pin "K") (pinfunction "C_K") (pintype "passive"))
      (node (ref "LED84") (pin "K") (pinfunction "C_K") (pintype "passive"))
      (node (ref "LED85") (pin "K") (pinfunction "C_K") (pintype "passive"))
      (node (ref "LED86") (pin "K") (pinfunction "C_K") (pintype "passive"))
      (node (ref "LED87") (pin "K") (pinfunction "C_K") (pintype "passive"))
      (node (ref "LED88") (pin "K") (pinfunction "C_K") (pintype "passive"))
      (node (ref "LED89") (pin "K") (pinfunction "C_K") (pintype "passive"))
      (node (ref "LED9") (pin "K") (pinfunction "C_K") (pintype "passive"))
      (node (ref "LED90") (pin "K") (pinfunction "C_K") (pintype "passive"))
      (node (ref "LED91") (pin "K") (pinfunction "C_K") (pintype "passive"))
      (node (ref "LED92") (pin "K") (pinfunction "C_K") (pintype "passive"))
      (node (ref "LED93") (pin "K") (pinfunction "C_K") (pintype "passive"))
      (node (ref "LED94") (pin "K") (pinfunction "C_K") (pintype "passive"))
      (node (ref "LED95") (pin "K") (pinfunction "C_K") (pintype "passive"))
      (node (ref "LED96") (pin "K") (pinfunction "C_K") (pintype "passive"))
      (node (ref "Q19") (pin "E") (pinfunction "E_E") (pintype "passive"))
      (node (ref "Q20") (pin "E") (pinfunction "E_E") (pintype "passive"))
    )
    (net (code "3") (name "GND1") (class "Default")
      (node (ref "D2") (pin "A") (pinfunction "A_A") (pintype "passive"))
      (node (ref "D6") (pin "A") (pinfunction "A_A") (pintype "passive"))
      (node (ref "JP4") (pin "4") (pinfunction "4_4") (pintype "passive"))
      (node (ref "JP8") (pin "9") (pinfunction "9_9") (pintype "passive"))
      (node (ref "LED97") (pin "K") (pinfunction "C_K") (pintype "passive"))
      (node (ref "OK1") (pin "2") (pinfunction "C_2") (pintype "passive"))
      (node (ref "OK1") (pin "3") (pinfunction "EMIT_3") (pintype "passive"))
      (node (ref "OK2") (pin "2") (pinfunction "C_2") (pintype "passive"))
      (node (ref "OK2") (pin "3") (pinfunction "EMIT_3") (pintype "passive"))
      (node (ref "Q13") (pin "S") (pinfunction "S_S") (pintype "passive"))
      (node (ref "Q14") (pin "S") (pinfunction "S_S") (pintype "passive"))
      (node (ref "Q15") (pin "E") (pinfunction "E_E") (pintype "passive"))
      (node (ref "Q16") (pin "E") (pinfunction "E_E") (pintype "passive"))
      (node (ref "R3") (pin "1") (pinfunction "1_1") (pintype "passive"))
      (node (ref "R7") (pin "1") (pinfunction "1_1") (pintype "passive"))
    )
    (net (code "4") (name "Net-(C1-Pad1)") (class "Default")
      (node (ref "C1") (pin "1") (pinfunction "1_1") (pintype "passive"))
      (node (ref "D1") (pin "A") (pinfunction "A_A") (pintype "passive"))
      (node (ref "D2") (pin "C") (pinfunction "C_C") (pintype "passive"))
      (node (ref "Q13") (pin "D") (pinfunction "D_D") (pintype "passive"))
      (node (ref "Q17") (pin "D") (pinfunction "D_D") (pintype "passive"))
      (node (ref "SV2") (pin "3") (pinfunction "3_3") (pintype "passive"))
    )
    (net (code "5") (name "Net-(C1-Pad2)") (class "Default")
      (node (ref "C1") (pin "2") (pinfunction "2_2") (pintype "passive"))
      (node (ref "C2") (pin "1") (pinfunction "1_1") (pintype "passive"))
    )
    (net (code "6") (name "Net-(C2-Pad2)") (class "Default")
      (node (ref "C2") (pin "2") (pinfunction "2_2") (pintype "passive"))
      (node (ref "D5") (pin "A") (pinfunction "A_A") (pintype "passive"))
      (node (ref "D6") (pin "C") (pinfunction "C_C") (pintype "passive"))
      (node (ref "Q14") (pin "D") (pinfunction "D_D") (pintype "passive"))
      (node (ref "Q18") (pin "D") (pinfunction "D_D") (pintype "passive"))
      (node (ref "SV2") (pin "1") (pinfunction "1_1") (pintype "passive"))
    )
    (net (code "7") (name "Net-(C3-Pad1)") (class "Default")
      (node (ref "C3") (pin "1") (pinfunction "1_1") (pintype "passive"))
      (node (ref "D3") (pin "A") (pinfunction "A_A") (pintype "passive"))
      (node (ref "D4") (pin "C") (pinfunction "C_C") (pintype "passive"))
      (node (ref "Q1") (pin "D") (pinfunction "D_D") (pintype "passive"))
      (node (ref "Q3") (pin "D") (pinfunction "D_D") (pintype "passive"))
      (node (ref "SV1") (pin "3") (pinfunction "3_3") (pintype "passive"))
    )
    (net (code "8") (name "Net-(C3-Pad2)") (class "Default")
      (node (ref "C3") (pin "2") (pinfunction "2_2") (pintype "passive"))
      (node (ref "C4") (pin "1") (pinfunction "1_1") (pintype "passive"))
    )
    (net (code "9") (name "Net-(C4-Pad2)") (class "Default")
      (node (ref "C4") (pin "2") (pinfunction "2_2") (pintype "passive"))
      (node (ref "D7") (pin "A") (pinfunction "A_A") (pintype "passive"))
      (node (ref "D8") (pin "C") (pinfunction "C_C") (pintype "passive"))
      (node (ref "Q2") (pin "D") (pinfunction "D_D") (pintype "passive"))
      (node (ref "Q4") (pin "D") (pinfunction "D_D") (pintype "passive"))
      (node (ref "SV1") (pin "1") (pinfunction "1_1") (pintype "passive"))
    )
    (net (code "10") (name "Net-(C5-Pad1)") (class "Default")
      (node (ref "C5") (pin "1") (pinfunction "1_1") (pintype "passive"))
      (node (ref "D10") (pin "C") (pinfunction "C_C") (pintype "passive"))
      (node (ref "D9") (pin "A") (pinfunction "A_A") (pintype "passive"))
      (node (ref "Q5") (pin "D") (pinfunction "D_D") (pintype "passive"))
      (node (ref "Q7") (pin "D") (pinfunction "D_D") (pintype "passive"))
      (node (ref "SV3") (pin "3") (pinfunction "3_3") (pintype "passive"))
    )
    (net (code "11") (name "Net-(C5-Pad2)") (class "Default")
      (node (ref "C5") (pin "2") (pinfunction "2_2") (pintype "passive"))
      (node (ref "C6") (pin "1") (pinfunction "1_1") (pintype "passive"))
    )
    (net (code "12") (name "Net-(C6-Pad2)") (class "Default")
      (node (ref "C6") (pin "2") (pinfunction "2_2") (pintype "passive"))
      (node (ref "D11") (pin "A") (pinfunction "A_A") (pintype "passive"))
      (node (ref "D12") (pin "C") (pinfunction "C_C") (pintype "passive"))
      (node (ref "Q6") (pin "D") (pinfunction "D_D") (pintype "passive"))
      (node (ref "Q8") (pin "D") (pinfunction "D_D") (pintype "passive"))
      (node (ref "SV3") (pin "1") (pinfunction "1_1") (pintype "passive"))
    )
    (net (code "13") (name "Net-(C7-Pad1)") (class "Default")
      (node (ref "C7") (pin "1") (pinfunction "1_1") (pintype "passive"))
      (node (ref "D13") (pin "A") (pinfunction "A_A") (pintype "passive"))
      (node (ref "D14") (pin "C") (pinfunction "C_C") (pintype "passive"))
      (node (ref "Q11") (pin "D") (pinfunction "D_D") (pintype "passive"))
      (node (ref "Q9") (pin "D") (pinfunction "D_D") (pintype "passive"))
      (node (ref "SV4") (pin "3") (pinfunction "3_3") (pintype "passive"))
    )
    (net (code "14") (name "Net-(C7-Pad2)") (class "Default")
      (node (ref "C7") (pin "2") (pinfunction "2_2") (pintype "passive"))
      (node (ref "C8") (pin "1") (pinfunction "1_1") (pintype "passive"))
    )
    (net (code "15") (name "Net-(C8-Pad2)") (class "Default")
      (node (ref "C8") (pin "2") (pinfunction "2_2") (pintype "passive"))
      (node (ref "D15") (pin "A") (pinfunction "A_A") (pintype "passive"))
      (node (ref "D16") (pin "C") (pinfunction "C_C") (pintype "passive"))
      (node (ref "Q10") (pin "D") (pinfunction "D_D") (pintype "passive"))
      (node (ref "Q12") (pin "D") (pinfunction "D_D") (pintype "passive"))
      (node (ref "SV4") (pin "1") (pinfunction "1_1") (pintype "passive"))
    )
    (net (code "16") (name "Net-(D1-PadC)") (class "Default")
      (node (ref "D1") (pin "C") (pinfunction "C_C") (pintype "passive"))
      (node (ref "D5") (pin "C") (pinfunction "C_C") (pintype "passive"))
      (node (ref "JP4") (pin "1") (pinfunction "1_1") (pintype "passive"))
      (node (ref "Q17") (pin "S") (pinfunction "S_S") (pintype "passive"))
      (node (ref "Q18") (pin "S") (pinfunction "S_S") (pintype "passive"))
      (node (ref "R5") (pin "2") (pinfunction "2_2") (pintype "passive"))
      (node (ref "R6") (pin "2") (pinfunction "2_2") (pintype "passive"))
      (node (ref "R8") (pin "2") (pinfunction "2_2") (pintype "passive"))
    )
    (net (code "17") (name "Net-(D3-PadC)") (class "Default")
      (node (ref "D3") (pin "C") (pinfunction "C_C") (pintype "passive"))
      (node (ref "D7") (pin "C") (pinfunction "C_C") (pintype "passive"))
      (node (ref "JP5") (pin "1") (pinfunction "1_1") (pintype "passive"))
      (node (ref "Q3") (pin "S") (pinfunction "S_S") (pintype "passive"))
      (node (ref "Q4") (pin "S") (pinfunction "S_S") (pintype "passive"))
      (node (ref "R10") (pin "2") (pinfunction "2_2") (pintype "passive"))
      (node (ref "R11") (pin "2") (pinfunction "2_2") (pintype "passive"))
      (node (ref "R14") (pin "2") (pinfunction "2_2") (pintype "passive"))
    )
    (net (code "18") (name "Net-(D11-PadC)") (class "Default")
      (node (ref "D11") (pin "C") (pinfunction "C_C") (pintype "passive"))
      (node (ref "D9") (pin "C") (pinfunction "C_C") (pintype "passive"))
      (node (ref "JP6") (pin "1") (pinfunction "1_1") (pintype "passive"))
      (node (ref "Q7") (pin "S") (pinfunction "S_S") (pintype "passive"))
      (node (ref "Q8") (pin "S") (pinfunction "S_S") (pintype "passive"))
      (node (ref "R17") (pin "2") (pinfunction "2_2") (pintype "passive"))
      (node (ref "R18") (pin "2") (pinfunction "2_2") (pintype "passive"))
      (node (ref "R21") (pin "2") (pinfunction "2_2") (pintype "passive"))
    )
    (net (code "19") (name "Net-(D13-PadC)") (class "Default")
      (node (ref "D13") (pin "C") (pinfunction "C_C") (pintype "passive"))
      (node (ref "D15") (pin "C") (pinfunction "C_C") (pintype "passive"))
      (node (ref "JP7") (pin "1") (pinfunction "1_1") (pintype "passive"))
      (node (ref "Q11") (pin "S") (pinfunction "S_S") (pintype "passive"))
      (node (ref "Q12") (pin "S") (pinfunction "S_S") (pintype "passive"))
      (node (ref "R24") (pin "2") (pinfunction "2_2") (pintype "passive"))
      (node (ref "R25") (pin "2") (pinfunction "2_2") (pintype "passive"))
      (node (ref "R28") (pin "2") (pinfunction "2_2") (pintype "passive"))
    )
    (net (code "20") (name "Net-(IC1A-A)") (class "Default")
      (node (ref "IC1") (pin "11") (pinfunction "A_11") (pintype "input"))
      (node (ref "JP1") (pin "1") (pinfunction "1_1") (pintype "passive"))
    )
    (net (code "21") (name "Net-(IC1A-B)") (class "Default")
      (node (ref "IC1") (pin "10") (pinfunction "B_10") (pintype "input"))
      (node (ref "JP1") (pin "2") (pinfunction "2_2") (pintype "passive"))
    )
    (net (code "22") (name "Net-(IC1A-C)") (class "Default")
      (node (ref "IC1") (pin "9") (pinfunction "C_9") (pintype "input"))
      (node (ref "JP1") (pin "3") (pinfunction "3_3") (pintype "passive"))
    )
    (net (code "23") (name "Net-(IC1A-X)") (class "Default")
      (node (ref "IC1") (pin "3") (pinfunction "X_3") (pintype "bidirectional"))
      (node (ref "JP1") (pin "8") (pinfunction "8_8") (pintype "passive"))
    )
    (net (code "24") (name "Net-(IC1A-X0)") (class "Default")
      (node (ref "IC1") (pin "13") (pinfunction "X0_13") (pintype "bidirectional"))
      (node (ref "LED32") (pin "A") (pinfunction "A_A") (pintype "passive"))
      (node (ref "RN4") (pin "9") (pinfunction "9_9") (pintype "passive"))
    )
    (net (code "25") (name "Net-(IC1A-X1)") (class "Default")
      (node (ref "IC1") (pin "14") (pinfunction "X1_14") (pintype "bidirectional"))
      (node (ref "LED31") (pin "A") (pinfunction "A_A") (pintype "passive"))
      (node (ref "RN4") (pin "8") (pinfunction "8_8") (pintype "passive"))
    )
    (net (code "26") (name "Net-(IC1A-X2)") (class "Default")
      (node (ref "IC1") (pin "15") (pinfunction "X2_15") (pintype "bidirectional"))
      (node (ref "LED30") (pin "A") (pinfunction "A_A") (pintype "passive"))
      (node (ref "RN4") (pin "7") (pinfunction "7_7") (pintype "passive"))
    )
    (net (code "27") (name "Net-(IC1A-X3)") (class "Default")
      (node (ref "IC1") (pin "12") (pinfunction "X3_12") (pintype "bidirectional"))
      (node (ref "LED29") (pin "A") (pinfunction "A_A") (pintype "passive"))
      (node (ref "RN4") (pin "6") (pinfunction "6_6") (pintype "passive"))
    )
    (net (code "28") (name "Net-(IC1A-X4)") (class "Default")
      (node (ref "IC1") (pin "1") (pinfunction "X4_1") (pintype "bidirectional"))
      (node (ref "LED28") (pin "A") (pinfunction "A_A") (pintype "passive"))
      (node (ref "RN4") (pin "5") (pinfunction "5_5") (pintype "passive"))
    )
    (net (code "29") (name "Net-(IC1A-X5)") (class "Default")
      (node (ref "IC1") (pin "5") (pinfunction "X5_5") (pintype "bidirectional"))
      (node (ref "LED27") (pin "A") (pinfunction "A_A") (pintype "passive"))
      (node (ref "RN4") (pin "4") (pinfunction "4_4") (pintype "passive"))
    )
    (net (code "30") (name "Net-(IC1A-X6)") (class "Default")
      (node (ref "IC1") (pin "2") (pinfunction "X6_2") (pintype "bidirectional"))
      (node (ref "LED26") (pin "A") (pinfunction "A_A") (pintype "passive"))
      (node (ref "RN4") (pin "3") (pinfunction "3_3") (pintype "passive"))
    )
    (net (code "31") (name "Net-(IC1A-X7)") (class "Default")
      (node (ref "IC1") (pin "4") (pinfunction "X7_4") (pintype "bidirectional"))
      (node (ref "LED25") (pin "A") (pinfunction "A_A") (pintype "passive"))
      (node (ref "RN4") (pin "2") (pinfunction "2_2") (pintype "passive"))
    )
    (net (code "32") (name "Net-(IC2A-A)") (class "Default")
      (node (ref "IC2") (pin "11") (pinfunction "A_11") (pintype "input"))
      (node (ref "JP1") (pin "6") (pinfunction "6_6") (pintype "passive"))
    )
    (net (code "33") (name "Net-(IC2A-B)") (class "Default")
      (node (ref "IC2") (pin "10") (pinfunction "B_10") (pintype "input"))
      (node (ref "JP1") (pin "5") (pinfunction "5_5") (pintype "passive"))
    )
    (net (code "34") (name "Net-(IC2A-C)") (class "Default")
      (node (ref "IC2") (pin "9") (pinfunction "C_9") (pintype "input"))
      (node (ref "JP1") (pin "4") (pinfunction "4_4") (pintype "passive"))
    )
    (net (code "35") (name "Net-(IC2A-X)") (class "Default")
      (node (ref "IC2") (pin "3") (pinfunction "X_3") (pintype "bidirectional"))
      (node (ref "JP1") (pin "7") (pinfunction "7_7") (pintype "passive"))
    )
    (net (code "36") (name "Net-(IC2A-X0)") (class "Default")
      (node (ref "IC2") (pin "13") (pinfunction "X0_13") (pintype "bidirectional"))
      (node (ref "LED24") (pin "A") (pinfunction "A_A") (pintype "passive"))
      (node (ref "RN3") (pin "9") (pinfunction "9_9") (pintype "passive"))
    )
    (net (code "37") (name "Net-(IC2A-X1)") (class "Default")
      (node (ref "IC2") (pin "14") (pinfunction "X1_14") (pintype "bidirectional"))
      (node (ref "LED23") (pin "A") (pinfunction "A_A") (pintype "passive"))
      (node (ref "RN3") (pin "8") (pinfunction "8_8") (pintype "passive"))
    )
    (net (code "38") (name "Net-(IC2A-X2)") (class "Default")
      (node (ref "IC2") (pin "15") (pinfunction "X2_15") (pintype "bidirectional"))
      (node (ref "LED22") (pin "A") (pinfunction "A_A") (pintype "passive"))
      (node (ref "RN3") (pin "7") (pinfunction "7_7") (pintype "passive"))
    )
    (net (code "39") (name "Net-(IC2A-X3)") (class "Default")
      (node (ref "IC2") (pin "12") (pinfunction "X3_12") (pintype "bidirectional"))
      (node (ref "LED21") (pin "A") (pinfunction "A_A") (pintype "passive"))
      (node (ref "RN3") (pin "6") (pinfunction "6_6") (pintype "passive"))
    )
    (net (code "40") (name "Net-(IC2A-X4)") (class "Default")
      (node (ref "IC2") (pin "1") (pinfunction "X4_1") (pintype "bidirectional"))
      (node (ref "LED20") (pin "A") (pinfunction "A_A") (pintype "passive"))
      (node (ref "RN3") (pin "5") (pinfunction "5_5") (pintype "passive"))
    )
    (net (code "41") (name "Net-(IC2A-X5)") (class "Default")
      (node (ref "IC2") (pin "5") (pinfunction "X5_5") (pintype "bidirectional"))
      (node (ref "LED19") (pin "A") (pinfunction "A_A") (pintype "passive"))
      (node (ref "RN3") (pin "4") (pinfunction "4_4") (pintype "passive"))
    )
    (net (code "42") (name "Net-(IC2A-X6)") (class "Default")
      (node (ref "IC2") (pin "2") (pinfunction "X6_2") (pintype "bidirectional"))
      (node (ref "LED18") (pin "A") (pinfunction "A_A") (pintype "passive"))
      (node (ref "RN3") (pin "3") (pinfunction "3_3") (pintype "passive"))
    )
    (net (code "43") (name "Net-(IC2A-X7)") (class "Default")
      (node (ref "IC2") (pin "4") (pinfunction "X7_4") (pintype "bidirectional"))
      (node (ref "LED17") (pin "A") (pinfunction "A_A") (pintype "passive"))
      (node (ref "RN3") (pin "2") (pinfunction "2_2") (pintype "passive"))
    )
    (net (code "44") (name "Net-(IC3A-A)") (class "Default")
      (node (ref "IC3") (pin "11") (pinfunction "A_11") (pintype "input"))
      (node (ref "JP2") (pin "1") (pinfunction "1_1") (pintype "passive"))
    )
    (net (code "45") (name "Net-(IC3A-B)") (class "Default")
      (node (ref "IC3") (pin "10") (pinfunction "B_10") (pintype "input"))
      (node (ref "JP2") (pin "2") (pinfunction "2_2") (pintype "passive"))
    )
    (net (code "46") (name "Net-(IC3A-C)") (class "Default")
      (node (ref "IC3") (pin "9") (pinfunction "C_9") (pintype "input"))
      (node (ref "JP2") (pin "3") (pinfunction "3_3") (pintype "passive"))
    )
    (net (code "47") (name "Net-(IC3A-X)") (class "Default")
      (node (ref "IC3") (pin "3") (pinfunction "X_3") (pintype "bidirectional"))
      (node (ref "JP2") (pin "8") (pinfunction "8_8") (pintype "passive"))
    )
    (net (code "48") (name "Net-(IC3A-X0)") (class "Default")
      (node (ref "IC3") (pin "13") (pinfunction "X0_13") (pintype "bidirectional"))
      (node (ref "LED64") (pin "A") (pinfunction "A_A") (pintype "passive"))
      (node (ref "RN8") (pin "9") (pinfunction "9_9") (pintype "passive"))
    )
    (net (code "49") (name "Net-(IC3A-X1)") (class "Default")
      (node (ref "IC3") (pin "14") (pinfunction "X1_14") (pintype "bidirectional"))
      (node (ref "LED63") (pin "A") (pinfunction "A_A") (pintype "passive"))
      (node (ref "RN8") (pin "8") (pinfunction "8_8") (pintype "passive"))
    )
    (net (code "50") (name "Net-(IC3A-X2)") (class "Default")
      (node (ref "IC3") (pin "15") (pinfunction "X2_15") (pintype "bidirectional"))
      (node (ref "LED62") (pin "A") (pinfunction "A_A") (pintype "passive"))
      (node (ref "RN8") (pin "7") (pinfunction "7_7") (pintype "passive"))
    )
    (net (code "51") (name "Net-(IC3A-X3)") (class "Default")
      (node (ref "IC3") (pin "12") (pinfunction "X3_12") (pintype "bidirectional"))
      (node (ref "LED61") (pin "A") (pinfunction "A_A") (pintype "passive"))
      (node (ref "RN8") (pin "6") (pinfunction "6_6") (pintype "passive"))
    )
    (net (code "52") (name "Net-(IC3A-X4)") (class "Default")
      (node (ref "IC3") (pin "1") (pinfunction "X4_1") (pintype "bidirectional"))
      (node (ref "LED60") (pin "A") (pinfunction "A_A") (pintype "passive"))
      (node (ref "RN8") (pin "5") (pinfunction "5_5") (pintype "passive"))
    )
    (net (code "53") (name "Net-(IC3A-X5)") (class "Default")
      (node (ref "IC3") (pin "5") (pinfunction "X5_5") (pintype "bidirectional"))
      (node (ref "LED59") (pin "A") (pinfunction "A_A") (pintype "passive"))
      (node (ref "RN8") (pin "4") (pinfunction "4_4") (pintype "passive"))
    )
    (net (code "54") (name "Net-(IC3A-X6)") (class "Default")
      (node (ref "IC3") (pin "2") (pinfunction "X6_2") (pintype "bidirectional"))
      (node (ref "LED58") (pin "A") (pinfunction "A_A") (pintype "passive"))
      (node (ref "RN8") (pin "3") (pinfunction "3_3") (pintype "passive"))
    )
    (net (code "55") (name "Net-(IC3A-X7)") (class "Default")
      (node (ref "IC3") (pin "4") (pinfunction "X7_4") (pintype "bidirectional"))
      (node (ref "LED57") (pin "A") (pinfunction "A_A") (pintype "passive"))
      (node (ref "RN8") (pin "2") (pinfunction "2_2") (pintype "passive"))
    )
    (net (code "56") (name "Net-(IC4A-A)") (class "Default")
      (node (ref "IC4") (pin "11") (pinfunction "A_11") (pintype "input"))
      (node (ref "JP2") (pin "6") (pinfunction "6_6") (pintype "passive"))
    )
    (net (code "57") (name "Net-(IC4A-B)") (class "Default")
      (node (ref "IC4") (pin "10") (pinfunction "B_10") (pintype "input"))
      (node (ref "JP2") (pin "5") (pinfunction "5_5") (pintype "passive"))
    )
    (net (code "58") (name "Net-(IC4A-C)") (class "Default")
      (node (ref "IC4") (pin "9") (pinfunction "C_9") (pintype "input"))
      (node (ref "JP2") (pin "4") (pinfunction "4_4") (pintype "passive"))
    )
    (net (code "59") (name "Net-(IC4A-X)") (class "Default")
      (node (ref "IC4") (pin "3") (pinfunction "X_3") (pintype "bidirectional"))
      (node (ref "JP2") (pin "7") (pinfunction "7_7") (pintype "passive"))
    )
    (net (code "60") (name "Net-(IC4A-X0)") (class "Default")
      (node (ref "IC4") (pin "13") (pinfunction "X0_13") (pintype "bidirectional"))
      (node (ref "LED56") (pin "A") (pinfunction "A_A") (pintype "passive"))
      (node (ref "RN7") (pin "9") (pinfunction "9_9") (pintype "passive"))
    )
    (net (code "61") (name "Net-(IC4A-X1)") (class "Default")
      (node (ref "IC4") (pin "14") (pinfunction "X1_14") (pintype "bidirectional"))
      (node (ref "LED55") (pin "A") (pinfunction "A_A") (pintype "passive"))
      (node (ref "RN7") (pin "8") (pinfunction "8_8") (pintype "passive"))
    )
    (net (code "62") (name "Net-(IC4A-X2)") (class "Default")
      (node (ref "IC4") (pin "15") (pinfunction "X2_15") (pintype "bidirectional"))
      (node (ref "LED54") (pin "A") (pinfunction "A_A") (pintype "passive"))
      (node (ref "RN7") (pin "7") (pinfunction "7_7") (pintype "passive"))
    )
    (net (code "63") (name "Net-(IC4A-X3)") (class "Default")
      (node (ref "IC4") (pin "12") (pinfunction "X3_12") (pintype "bidirectional"))
      (node (ref "LED53") (pin "A") (pinfunction "A_A") (pintype "passive"))
      (node (ref "RN7") (pin "6") (pinfunction "6_6") (pintype "passive"))
    )
    (net (code "64") (name "Net-(IC4A-X4)") (class "Default")
      (node (ref "IC4") (pin "1") (pinfunction "X4_1") (pintype "bidirectional"))
      (node (ref "LED52") (pin "A") (pinfunction "A_A") (pintype "passive"))
      (node (ref "RN7") (pin "5") (pinfunction "5_5") (pintype "passive"))
    )
    (net (code "65") (name "Net-(IC4A-X5)") (class "Default")
      (node (ref "IC4") (pin "5") (pinfunction "X5_5") (pintype "bidirectional"))
      (node (ref "LED51") (pin "A") (pinfunction "A_A") (pintype "passive"))
      (node (ref "RN7") (pin "4") (pinfunction "4_4") (pintype "passive"))
    )
    (net (code "66") (name "Net-(IC4A-X6)") (class "Default")
      (node (ref "IC4") (pin "2") (pinfunction "X6_2") (pintype "bidirectional"))
      (node (ref "LED50") (pin "A") (pinfunction "A_A") (pintype "passive"))
      (node (ref "RN7") (pin "3") (pinfunction "3_3") (pintype "passive"))
    )
    (net (code "67") (name "Net-(IC4A-X7)") (class "Default")
      (node (ref "IC4") (pin "4") (pinfunction "X7_4") (pintype "bidirectional"))
      (node (ref "LED49") (pin "A") (pinfunction "A_A") (pintype "passive"))
      (node (ref "RN7") (pin "2") (pinfunction "2_2") (pintype "passive"))
    )
    (net (code "68") (name "Net-(IC5A-A)") (class "Default")
      (node (ref "IC5") (pin "11") (pinfunction "A_11") (pintype "input"))
      (node (ref "JP3") (pin "1") (pinfunction "1_1") (pintype "passive"))
    )
    (net (code "69") (name "Net-(IC5A-B)") (class "Default")
      (node (ref "IC5") (pin "10") (pinfunction "B_10") (pintype "input"))
      (node (ref "JP3") (pin "2") (pinfunction "2_2") (pintype "passive"))
    )
    (net (code "70") (name "Net-(IC5A-C)") (class "Default")
      (node (ref "IC5") (pin "9") (pinfunction "C_9") (pintype "input"))
      (node (ref "JP3") (pin "3") (pinfunction "3_3") (pintype "passive"))
    )
    (net (code "71") (name "Net-(IC5A-X)") (class "Default")
      (node (ref "IC5") (pin "3") (pinfunction "X_3") (pintype "bidirectional"))
      (node (ref "JP3") (pin "8") (pinfunction "8_8") (pintype "passive"))
    )
    (net (code "72") (name "Net-(IC5A-X0)") (class "Default")
      (node (ref "IC5") (pin "13") (pinfunction "X0_13") (pintype "bidirectional"))
      (node (ref "LED96") (pin "A") (pinfunction "A_A") (pintype "passive"))
      (node (ref "RN12") (pin "9") (pinfunction "9_9") (pintype "passive"))
    )
    (net (code "73") (name "Net-(IC5A-X1)") (class "Default")
      (node (ref "IC5") (pin "14") (pinfunction "X1_14") (pintype "bidirectional"))
      (node (ref "LED95") (pin "A") (pinfunction "A_A") (pintype "passive"))
      (node (ref "RN12") (pin "8") (pinfunction "8_8") (pintype "passive"))
    )
    (net (code "74") (name "Net-(IC5A-X2)") (class "Default")
      (node (ref "IC5") (pin "15") (pinfunction "X2_15") (pintype "bidirectional"))
      (node (ref "LED94") (pin "A") (pinfunction "A_A") (pintype "passive"))
      (node (ref "RN12") (pin "7") (pinfunction "7_7") (pintype "passive"))
    )
    (net (code "75") (name "Net-(IC5A-X3)") (class "Default")
      (node (ref "IC5") (pin "12") (pinfunction "X3_12") (pintype "bidirectional"))
      (node (ref "LED93") (pin "A") (pinfunction "A_A") (pintype "passive"))
      (node (ref "RN12") (pin "6") (pinfunction "6_6") (pintype "passive"))
    )
    (net (code "76") (name "Net-(IC5A-X4)") (class "Default")
      (node (ref "IC5") (pin "1") (pinfunction "X4_1") (pintype "bidirectional"))
      (node (ref "LED92") (pin "A") (pinfunction "A_A") (pintype "passive"))
      (node (ref "RN12") (pin "5") (pinfunction "5_5") (pintype "passive"))
    )
    (net (code "77") (name "Net-(IC5A-X5)") (class "Default")
      (node (ref "IC5") (pin "5") (pinfunction "X5_5") (pintype "bidirectional"))
      (node (ref "LED91") (pin "A") (pinfunction "A_A") (pintype "passive"))
      (node (ref "RN12") (pin "4") (pinfunction "4_4") (pintype "passive"))
    )
    (net (code "78") (name "Net-(IC5A-X6)") (class "Default")
      (node (ref "IC5") (pin "2") (pinfunction "X6_2") (pintype "bidirectional"))
      (node (ref "LED90") (pin "A") (pinfunction "A_A") (pintype "passive"))
      (node (ref "RN12") (pin "3") (pinfunction "3_3") (pintype "passive"))
    )
    (net (code "79") (name "Net-(IC5A-X7)") (class "Default")
      (node (ref "IC5") (pin "4") (pinfunction "X7_4") (pintype "bidirectional"))
      (node (ref "LED89") (pin "A") (pinfunction "A_A") (pintype "passive"))
      (node (ref "RN12") (pin "2") (pinfunction "2_2") (pintype "passive"))
    )
    (net (code "80") (name "Net-(IC6A-A)") (class "Default")
      (node (ref "IC6") (pin "11") (pinfunction "A_11") (pintype "input"))
      (node (ref "JP3") (pin "6") (pinfunction "6_6") (pintype "passive"))
    )
    (net (code "81") (name "Net-(IC6A-B)") (class "Default")
      (node (ref "IC6") (pin "10") (pinfunction "B_10") (pintype "input"))
      (node (ref "JP3") (pin "5") (pinfunction "5_5") (pintype "passive"))
    )
    (net (code "82") (name "Net-(IC6A-C)") (class "Default")
      (node (ref "IC6") (pin "9") (pinfunction "C_9") (pintype "input"))
      (node (ref "JP3") (pin "4") (pinfunction "4_4") (pintype "passive"))
    )
    (net (code "83") (name "Net-(IC6A-X)") (class "Default")
      (node (ref "IC6") (pin "3") (pinfunction "X_3") (pintype "bidirectional"))
      (node (ref "JP3") (pin "7") (pinfunction "7_7") (pintype "passive"))
    )
    (net (code "84") (name "Net-(IC6A-X0)") (class "Default")
      (node (ref "IC6") (pin "13") (pinfunction "X0_13") (pintype "bidirectional"))
      (node (ref "LED88") (pin "A") (pinfunction "A_A") (pintype "passive"))
      (node (ref "RN11") (pin "9") (pinfunction "9_9") (pintype "passive"))
    )
    (net (code "85") (name "Net-(IC6A-X1)") (class "Default")
      (node (ref "IC6") (pin "14") (pinfunction "X1_14") (pintype "bidirectional"))
      (node (ref "LED87") (pin "A") (pinfunction "A_A") (pintype "passive"))
      (node (ref "RN11") (pin "8") (pinfunction "8_8") (pintype "passive"))
    )
    (net (code "86") (name "Net-(IC6A-X2)") (class "Default")
      (node (ref "IC6") (pin "15") (pinfunction "X2_15") (pintype "bidirectional"))
      (node (ref "LED86") (pin "A") (pinfunction "A_A") (pintype "passive"))
      (node (ref "RN11") (pin "7") (pinfunction "7_7") (pintype "passive"))
    )
    (net (code "87") (name "Net-(IC6A-X3)") (class "Default")
      (node (ref "IC6") (pin "12") (pinfunction "X3_12") (pintype "bidirectional"))
      (node (ref "LED85") (pin "A") (pinfunction "A_A") (pintype "passive"))
      (node (ref "RN11") (pin "6") (pinfunction "6_6") (pintype "passive"))
    )
    (net (code "88") (name "Net-(IC6A-X4)") (class "Default")
      (node (ref "IC6") (pin "1") (pinfunction "X4_1") (pintype "bidirectional"))
      (node (ref "LED84") (pin "A") (pinfunction "A_A") (pintype "passive"))
      (node (ref "RN11") (pin "5") (pinfunction "5_5") (pintype "passive"))
    )
    (net (code "89") (name "Net-(IC6A-X5)") (class "Default")
      (node (ref "IC6") (pin "5") (pinfunction "X5_5") (pintype "bidirectional"))
      (node (ref "LED83") (pin "A") (pinfunction "A_A") (pintype "passive"))
      (node (ref "RN11") (pin "4") (pinfunction "4_4") (pintype "passive"))
    )
    (net (code "90") (name "Net-(IC6A-X6)") (class "Default")
      (node (ref "IC6") (pin "2") (pinfunction "X6_2") (pintype "bidirectional"))
      (node (ref "LED82") (pin "A") (pinfunction "A_A") (pintype "passive"))
      (node (ref "RN11") (pin "3") (pinfunction "3_3") (pintype "passive"))
    )
    (net (code "91") (name "Net-(IC6A-X7)") (class "Default")
      (node (ref "IC6") (pin "4") (pinfunction "X7_4") (pintype "bidirectional"))
      (node (ref "LED81") (pin "A") (pinfunction "A_A") (pintype "passive"))
      (node (ref "RN11") (pin "2") (pinfunction "2_2") (pintype "passive"))
    )
    (net (code "92") (name "Net-(JP4-Pad2)") (class "Default")
      (node (ref "JP4") (pin "2") (pinfunction "2_2") (pintype "passive"))
      (node (ref "R4") (pin "2") (pinfunction "2_2") (pintype "passive"))
    )
    (net (code "93") (name "Net-(JP4-Pad3)") (class "Default")
      (node (ref "JP4") (pin "3") (pinfunction "3_3") (pintype "passive"))
      (node (ref "R1") (pin "1") (pinfunction "1_1") (pintype "passive"))
    )
    (net (code "94") (name "Net-(JP5-Pad2)") (class "Default")
      (node (ref "JP5") (pin "2") (pinfunction "2_2") (pintype "passive"))
      (node (ref "R9") (pin "2") (pinfunction "2_2") (pintype "passive"))
    )
    (net (code "95") (name "Net-(JP5-Pad3)") (class "Default")
      (node (ref "JP5") (pin "3") (pinfunction "3_3") (pintype "passive"))
      (node (ref "R2") (pin "1") (pinfunction "1_1") (pintype "passive"))
    )
    (net (code "96") (name "Net-(JP6-Pad2)") (class "Default")
      (node (ref "JP6") (pin "2") (pinfunction "2_2") (pintype "passive"))
      (node (ref "R16") (pin "2") (pinfunction "2_2") (pintype "passive"))
    )
    (net (code "97") (name "Net-(JP6-Pad3)") (class "Default")
      (node (ref "JP6") (pin "3") (pinfunction "3_3") (pintype "passive"))
      (node (ref "R15") (pin "1") (pinfunction "1_1") (pintype "passive"))
    )
    (net (code "98") (name "Net-(JP7-Pad2)") (class "Default")
      (node (ref "JP7") (pin "2") (pinfunction "2_2") (pintype "passive"))
      (node (ref "R23") (pin "2") (pinfunction "2_2") (pintype "passive"))
    )
    (net (code "99") (name "Net-(JP7-Pad3)") (class "Default")
      (node (ref "JP7") (pin "3") (pinfunction "3_3") (pintype "passive"))
      (node (ref "R22") (pin "1") (pinfunction "1_1") (pintype "passive"))
    )
    (net (code "100") (name "Net-(JP8-Pad1)") (class "Default")
      (node (ref "JP8") (pin "1") (pinfunction "1_1") (pintype "passive"))
      (node (ref "R31") (pin "2") (pinfunction "2_2") (pintype "passive"))
    )
    (net (code "101") (name "Net-(JP8-Pad2)") (class "Default")
      (node (ref "JP8") (pin "2") (pinfunction "2_2") (pintype "passive"))
      (node (ref "R32") (pin "2") (pinfunction "2_2") (pintype "passive"))
    )
    (net (code "102") (name "Net-(JP8-Pad3)") (class "Default")
      (node (ref "JP8") (pin "3") (pinfunction "3_3") (pintype "passive"))
      (node (ref "LED113") (pin "A") (pinfunction "A_A") (pintype "passive"))
      (node (ref "LED124") (pin "A") (pinfunction "A_A") (pintype "passive"))
      (node (ref "RN13") (pin "9") (pinfunction "9_9") (pintype "passive"))
    )
    (net (code "103") (name "Net-(JP8-Pad4)") (class "Default")
      (node (ref "JP8") (pin "4") (pinfunction "4_4") (pintype "passive"))
      (node (ref "LED114") (pin "A") (pinfunction "A_A") (pintype "passive"))
      (node (ref "LED123") (pin "A") (pinfunction "A_A") (pintype "passive"))
      (node (ref "RN13") (pin "8") (pinfunction "8_8") (pintype "passive"))
    )
    (net (code "104") (name "Net-(JP8-Pad5)") (class "Default")
      (node (ref "JP8") (pin "5") (pinfunction "5_5") (pintype "passive"))
      (node (ref "LED115") (pin "A") (pinfunction "A_A") (pintype "passive"))
      (node (ref "LED122") (pin "A") (pinfunction "A_A") (pintype "passive"))
      (node (ref "RN13") (pin "7") (pinfunction "7_7") (pintype "passive"))
    )
    (net (code "105") (name "Net-(JP8-Pad6)") (class "Default")
      (node (ref "JP8") (pin "6") (pinfunction "6_6") (pintype "passive"))
      (node (ref "LED116") (pin "A") (pinfunction "A_A") (pintype "passive"))
      (node (ref "LED121") (pin "A") (pinfunction "A_A") (pintype "passive"))
      (node (ref "RN13") (pin "6") (pinfunction "6_6") (pintype "passive"))
    )
    (net (code "106") (name "Net-(JP8-Pad7)") (class "Default")
      (node (ref "JP8") (pin "7") (pinfunction "7_7") (pintype "passive"))
      (node (ref "LED117") (pin "A") (pinfunction "A_A") (pintype "passive"))
      (node (ref "LED120") (pin "A") (pinfunction "A_A") (pintype "passive"))
      (node (ref "RN13") (pin "5") (pinfunction "5_5") (pintype "passive"))
    )
    (net (code "107") (name "Net-(JP8-Pad8)") (class "Default")
      (node (ref "JP8") (pin "8") (pinfunction "8_8") (pintype "passive"))
      (node (ref "LED118") (pin "A") (pinfunction "A_A") (pintype "passive"))
      (node (ref "LED119") (pin "A") (pinfunction "A_A") (pintype "passive"))
      (node (ref "RN13") (pin "4") (pinfunction "4_4") (pintype "passive"))
    )
    (net (code "108") (name "Net-(JP9-Pad1)") (class "Default")
      (node (ref "JP9") (pin "1") (pinfunction "1_1") (pintype "passive"))
      (node (ref "R35") (pin "2") (pinfunction "2_2") (pintype "passive"))
    )
    (net (code "109") (name "Net-(JP9-Pad2)") (class "Default")
      (node (ref "JP9") (pin "2") (pinfunction "2_2") (pintype "passive"))
      (node (ref "R36") (pin "2") (pinfunction "2_2") (pintype "passive"))
    )
    (net (code "110") (name "Net-(JP9-Pad3)") (class "Default")
      (node (ref "JP9") (pin "3") (pinfunction "3_3") (pintype "passive"))
      (node (ref "LED137") (pin "A") (pinfunction "A_A") (pintype "passive"))
      (node (ref "LED148") (pin "A") (pinfunction "A_A") (pintype "passive"))
      (node (ref "RN14") (pin "7") (pinfunction "7_7") (pintype "passive"))
    )
    (net (code "111") (name "Net-(JP9-Pad4)") (class "Default")
      (node (ref "JP9") (pin "4") (pinfunction "4_4") (pintype "passive"))
      (node (ref "LED138") (pin "A") (pinfunction "A_A") (pintype "passive"))
      (node (ref "LED147") (pin "A") (pinfunction "A_A") (pintype "passive"))
      (node (ref "RN14") (pin "6") (pinfunction "6_6") (pintype "passive"))
    )
    (net (code "112") (name "Net-(JP9-Pad5)") (class "Default")
      (node (ref "JP9") (pin "5") (pinfunction "5_5") (pintype "passive"))
      (node (ref "LED139") (pin "A") (pinfunction "A_A") (pintype "passive"))
      (node (ref "LED146") (pin "A") (pinfunction "A_A") (pintype "passive"))
      (node (ref "RN14") (pin "5") (pinfunction "5_5") (pintype "passive"))
    )
    (net (code "113") (name "Net-(JP9-Pad6)") (class "Default")
      (node (ref "JP9") (pin "6") (pinfunction "6_6") (pintype "passive"))
      (node (ref "LED140") (pin "A") (pinfunction "A_A") (pintype "passive"))
      (node (ref "LED145") (pin "A") (pinfunction "A_A") (pintype "passive"))
      (node (ref "RN14") (pin "4") (pinfunction "4_4") (pintype "passive"))
    )
    (net (code "114") (name "Net-(JP9-Pad7)") (class "Default")
      (node (ref "JP9") (pin "7") (pinfunction "7_7") (pintype "passive"))
      (node (ref "LED141") (pin "A") (pinfunction "A_A") (pintype "passive"))
      (node (ref "LED144") (pin "A") (pinfunction "A_A") (pintype "passive"))
      (node (ref "RN14") (pin "3") (pinfunction "3_3") (pintype "passive"))
    )
    (net (code "115") (name "Net-(JP9-Pad8)") (class "Default")
      (node (ref "JP9") (pin "8") (pinfunction "8_8") (pintype "passive"))
      (node (ref "LED142") (pin "A") (pinfunction "A_A") (pintype "passive"))
      (node (ref "LED143") (pin "A") (pinfunction "A_A") (pintype "passive"))
      (node (ref "RN14") (pin "2") (pinfunction "2_2") (pintype "passive"))
    )
    (net (code "116") (name "Net-(LED1-PadA)") (class "Default")
      (node (ref "LED1") (pin "A") (pinfunction "A_A") (pintype "passive"))
      (node (ref "RN1") (pin "2") (pinfunction "2_2") (pintype "passive"))
    )
    (net (code "117") (name "Net-(LED2-PadA)") (class "Default")
      (node (ref "LED2") (pin "A") (pinfunction "A_A") (pintype "passive"))
      (node (ref "RN1") (pin "3") (pinfunction "3_3") (pintype "passive"))
    )
    (net (code "118") (name "Net-(LED3-PadA)") (class "Default")
      (node (ref "LED3") (pin "A") (pinfunction "A_A") (pintype "passive"))
      (node (ref "RN1") (pin "4") (pinfunction "4_4") (pintype "passive"))
    )
    (net (code "119") (name "Net-(LED4-PadA)") (class "Default")
      (node (ref "LED4") (pin "A") (pinfunction "A_A") (pintype "passive"))
      (node (ref "RN1") (pin "5") (pinfunction "5_5") (pintype "passive"))
    )
    (net (code "120") (name "Net-(LED5-PadA)") (class "Default")
      (node (ref "LED5") (pin "A") (pinfunction "A_A") (pintype "passive"))
      (node (ref "RN1") (pin "6") (pinfunction "6_6") (pintype "passive"))
    )
    (net (code "121") (name "Net-(LED6-PadA)") (class "Default")
      (node (ref "LED6") (pin "A") (pinfunction "A_A") (pintype "passive"))
      (node (ref "RN1") (pin "7") (pinfunction "7_7") (pintype "passive"))
    )
    (net (code "122") (name "Net-(LED7-PadA)") (class "Default")
      (node (ref "LED7") (pin "A") (pinfunction "A_A") (pintype "passive"))
      (node (ref "RN1") (pin "8") (pinfunction "8_8") (pintype "passive"))
    )
    (net (code "123") (name "Net-(LED8-PadA)") (class "Default")
      (node (ref "LED8") (pin "A") (pinfunction "A_A") (pintype "passive"))
      (node (ref "RN1") (pin "9") (pinfunction "9_9") (pintype "passive"))
    )
    (net (code "124") (name "Net-(LED9-PadA)") (class "Default")
      (node (ref "LED9") (pin "A") (pinfunction "A_A") (pintype "passive"))
      (node (ref "RN2") (pin "2") (pinfunction "2_2") (pintype "passive"))
    )
    (net (code "125") (name "Net-(LED10-PadA)") (class "Default")
      (node (ref "LED10") (pin "A") (pinfunction "A_A") (pintype "passive"))
      (node (ref "RN2") (pin "3") (pinfunction "3_3") (pintype "passive"))
    )
    (net (code "126") (name "Net-(LED11-PadA)") (class "Default")
      (node (ref "LED11") (pin "A") (pinfunction "A_A") (pintype "passive"))
      (node (ref "RN2") (pin "4") (pinfunction "4_4") (pintype "passive"))
    )
    (net (code "127") (name "Net-(LED12-PadA)") (class "Default")
      (node (ref "LED12") (pin "A") (pinfunction "A_A") (pintype "passive"))
      (node (ref "RN2") (pin "5") (pinfunction "5_5") (pintype "passive"))
    )
    (net (code "128") (name "Net-(LED13-PadA)") (class "Default")
      (node (ref "LED13") (pin "A") (pinfunction "A_A") (pintype "passive"))
      (node (ref "RN2") (pin "6") (pinfunction "6_6") (pintype "passive"))
    )
    (net (code "129") (name "Net-(LED14-PadA)") (class "Default")
      (node (ref "LED14") (pin "A") (pinfunction "A_A") (pintype "passive"))
      (node (ref "RN2") (pin "7") (pinfunction "7_7") (pintype "passive"))
    )
    (net (code "130") (name "Net-(LED15-PadA)") (class "Default")
      (node (ref "LED15") (pin "A") (pinfunction "A_A") (pintype "passive"))
      (node (ref "RN2") (pin "8") (pinfunction "8_8") (pintype "passive"))
    )
    (net (code "131") (name "Net-(LED16-PadA)") (class "Default")
      (node (ref "LED16") (pin "A") (pinfunction "A_A") (pintype "passive"))
      (node (ref "RN2") (pin "9") (pinfunction "9_9") (pintype "passive"))
    )
    (net (code "132") (name "Net-(LED33-PadA)") (class "Default")
      (node (ref "LED33") (pin "A") (pinfunction "A_A") (pintype "passive"))
      (node (ref "RN5") (pin "2") (pinfunction "2_2") (pintype "passive"))
    )
    (net (code "133") (name "Net-(LED34-PadA)") (class "Default")
      (node (ref "LED34") (pin "A") (pinfunction "A_A") (pintype "passive"))
      (node (ref "RN5") (pin "3") (pinfunction "3_3") (pintype "passive"))
    )
    (net (code "134") (name "Net-(LED35-PadA)") (class "Default")
      (node (ref "LED35") (pin "A") (pinfunction "A_A") (pintype "passive"))
      (node (ref "RN5") (pin "4") (pinfunction "4_4") (pintype "passive"))
    )
    (net (code "135") (name "Net-(LED36-PadA)") (class "Default")
      (node (ref "LED36") (pin "A") (pinfunction "A_A") (pintype "passive"))
      (node (ref "RN5") (pin "5") (pinfunction "5_5") (pintype "passive"))
    )
    (net (code "136") (name "Net-(LED37-PadA)") (class "Default")
      (node (ref "LED37") (pin "A") (pinfunction "A_A") (pintype "passive"))
      (node (ref "RN5") (pin "6") (pinfunction "6_6") (pintype "passive"))
    )
    (net (code "137") (name "Net-(LED38-PadA)") (class "Default")
      (node (ref "LED38") (pin "A") (pinfunction "A_A") (pintype "passive"))
      (node (ref "RN5") (pin "7") (pinfunction "7_7") (pintype "passive"))
    )
    (net (code "138") (name "Net-(LED39-PadA)") (class "Default")
      (node (ref "LED39") (pin "A") (pinfunction "A_A") (pintype "passive"))
      (node (ref "RN5") (pin "8") (pinfunction "8_8") (pintype "passive"))
    )
    (net (code "139") (name "Net-(LED40-PadA)") (class "Default")
      (node (ref "LED40") (pin "A") (pinfunction "A_A") (pintype "passive"))
      (node (ref "RN5") (pin "9") (pinfunction "9_9") (pintype "passive"))
    )
    (net (code "140") (name "Net-(LED41-PadA)") (class "Default")
      (node (ref "LED41") (pin "A") (pinfunction "A_A") (pintype "passive"))
      (node (ref "RN6") (pin "2") (pinfunction "2_2") (pintype "passive"))
    )
    (net (code "141") (name "Net-(LED42-PadA)") (class "Default")
      (node (ref "LED42") (pin "A") (pinfunction "A_A") (pintype "passive"))
      (node (ref "RN6") (pin "3") (pinfunction "3_3") (pintype "passive"))
    )
    (net (code "142") (name "Net-(LED43-PadA)") (class "Default")
      (node (ref "LED43") (pin "A") (pinfunction "A_A") (pintype "passive"))
      (node (ref "RN6") (pin "4") (pinfunction "4_4") (pintype "passive"))
    )
    (net (code "143") (name "Net-(LED44-PadA)") (class "Default")
      (node (ref "LED44") (pin "A") (pinfunction "A_A") (pintype "passive"))
      (node (ref "RN6") (pin "5") (pinfunction "5_5") (pintype "passive"))
    )
    (net (code "144") (name "Net-(LED45-PadA)") (class "Default")
      (node (ref "LED45") (pin "A") (pinfunction "A_A") (pintype "passive"))
      (node (ref "RN6") (pin "6") (pinfunction "6_6") (pintype "passive"))
    )
    (net (code "145") (name "Net-(LED46-PadA)") (class "Default")
      (node (ref "LED46") (pin "A") (pinfunction "A_A") (pintype "passive"))
      (node (ref "RN6") (pin "7") (pinfunction "7_7") (pintype "passive"))
    )
    (net (code "146") (name "Net-(LED47-PadA)") (class "Default")
      (node (ref "LED47") (pin "A") (pinfunction "A_A") (pintype "passive"))
      (node (ref "RN6") (pin "8") (pinfunction "8_8") (pintype "passive"))
    )
    (net (code "147") (name "Net-(LED48-PadA)") (class "Default")
      (node (ref "LED48") (pin "A") (pinfunction "A_A") (pintype "passive"))
      (node (ref "RN6") (pin "9") (pinfunction "9_9") (pintype "passive"))
    )
    (net (code "148") (name "Net-(LED65-PadA)") (class "Default")
      (node (ref "LED65") (pin "A") (pinfunction "A_A") (pintype "passive"))
      (node (ref "RN9") (pin "2") (pinfunction "2_2") (pintype "passive"))
    )
    (net (code "149") (name "Net-(LED66-PadA)") (class "Default")
      (node (ref "LED66") (pin "A") (pinfunction "A_A") (pintype "passive"))
      (node (ref "RN9") (pin "3") (pinfunction "3_3") (pintype "passive"))
    )
    (net (code "150") (name "Net-(LED67-PadA)") (class "Default")
      (node (ref "LED67") (pin "A") (pinfunction "A_A") (pintype "passive"))
      (node (ref "RN9") (pin "4") (pinfunction "4_4") (pintype "passive"))
    )
    (net (code "151") (name "Net-(LED68-PadA)") (class "Default")
      (node (ref "LED68") (pin "A") (pinfunction "A_A") (pintype "passive"))
      (node (ref "RN9") (pin "5") (pinfunction "5_5") (pintype "passive"))
    )
    (net (code "152") (name "Net-(LED69-PadA)") (class "Default")
      (node (ref "LED69") (pin "A") (pinfunction "A_A") (pintype "passive"))
      (node (ref "RN9") (pin "6") (pinfunction "6_6") (pintype "passive"))
    )
    (net (code "153") (name "Net-(LED70-PadA)") (class "Default")
      (node (ref "LED70") (pin "A") (pinfunction "A_A") (pintype "passive"))
      (node (ref "RN9") (pin "7") (pinfunction "7_7") (pintype "passive"))
    )
    (net (code "154") (name "Net-(LED71-PadA)") (class "Default")
      (node (ref "LED71") (pin "A") (pinfunction "A_A") (pintype "passive"))
      (node (ref "RN9") (pin "8") (pinfunction "8_8") (pintype "passive"))
    )
    (net (code "155") (name "Net-(LED72-PadA)") (class "Default")
      (node (ref "LED72") (pin "A") (pinfunction "A_A") (pintype "passive"))
      (node (ref "RN9") (pin "9") (pinfunction "9_9") (pintype "passive"))
    )
    (net (code "156") (name "Net-(LED73-PadA)") (class "Default")
      (node (ref "LED73") (pin "A") (pinfunction "A_A") (pintype "passive"))
      (node (ref "RN10") (pin "2") (pinfunction "2_2") (pintype "passive"))
    )
    (net (code "157") (name "Net-(LED74-PadA)") (class "Default")
      (node (ref "LED74") (pin "A") (pinfunction "A_A") (pintype "passive"))
      (node (ref "RN10") (pin "3") (pinfunction "3_3") (pintype "passive"))
    )
    (net (code "158") (name "Net-(LED75-PadA)") (class "Default")
      (node (ref "LED75") (pin "A") (pinfunction "A_A") (pintype "passive"))
      (node (ref "RN10") (pin "4") (pinfunction "4_4") (pintype "passive"))
    )
    (net (code "159") (name "Net-(LED76-PadA)") (class "Default")
      (node (ref "LED76") (pin "A") (pinfunction "A_A") (pintype "passive"))
      (node (ref "RN10") (pin "5") (pinfunction "5_5") (pintype "passive"))
    )
    (net (code "160") (name "Net-(LED77-PadA)") (class "Default")
      (node (ref "LED77") (pin "A") (pinfunction "A_A") (pintype "passive"))
      (node (ref "RN10") (pin "6") (pinfunction "6_6") (pintype "passive"))
    )
    (net (code "161") (name "Net-(LED78-PadA)") (class "Default")
      (node (ref "LED78") (pin "A") (pinfunction "A_A") (pintype "passive"))
      (node (ref "RN10") (pin "7") (pinfunction "7_7") (pintype "passive"))
    )
    (net (code "162") (name "Net-(LED79-PadA)") (class "Default")
      (node (ref "LED79") (pin "A") (pinfunction "A_A") (pintype "passive"))
      (node (ref "RN10") (pin "8") (pinfunction "8_8") (pintype "passive"))
    )
    (net (code "163") (name "Net-(LED80-PadA)") (class "Default")
      (node (ref "LED80") (pin "A") (pinfunction "A_A") (pintype "passive"))
      (node (ref "RN10") (pin "9") (pinfunction "9_9") (pintype "passive"))
    )
    (net (code "164") (name "Net-(LED97-PadA)") (class "Default")
      (node (ref "LED97") (pin "A") (pinfunction "A_A") (pintype "passive"))
      (node (ref "R8") (pin "1") (pinfunction "1_1") (pintype "passive"))
    )
    (net (code "165") (name "Net-(LED98-C)") (class "Default")
      (node (ref "D4") (pin "A") (pinfunction "A_A") (pintype "passive"))
      (node (ref "D8") (pin "A") (pinfunction "A_A") (pintype "passive"))
      (node (ref "JP5") (pin "4") (pinfunction "4_4") (pintype "passive"))
      (node (ref "LED98") (pin "K") (pinfunction "C_K") (pintype "passive"))
      (node (ref "OK3") (pin "2") (pinfunction "C_2") (pintype "passive"))
      (node (ref "OK3") (pin "3") (pinfunction "EMIT_3") (pintype "passive"))
      (node (ref "OK4") (pin "2") (pinfunction "C_2") (pintype "passive"))
      (node (ref "OK4") (pin "3") (pinfunction "EMIT_3") (pintype "passive"))
      (node (ref "Q1") (pin "S") (pinfunction "S_S") (pintype "passive"))
      (node (ref "Q2") (pin "S") (pinfunction "S_S") (pintype "passive"))
      (node (ref "R12") (pin "1") (pinfunction "1_1") (pintype "passive"))
      (node (ref "R13") (pin "1") (pinfunction "1_1") (pintype "passive"))
    )
    (net (code "166") (name "Net-(LED98-PadA)") (class "Default")
      (node (ref "LED98") (pin "A") (pinfunction "A_A") (pintype "passive"))
      (node (ref "R14") (pin "1") (pinfunction "1_1") (pintype "passive"))
    )
    (net (code "167") (name "Net-(LED99-C)") (class "Default")
      (node (ref "D10") (pin "A") (pinfunction "A_A") (pintype "passive"))
      (node (ref "D12") (pin "A") (pinfunction "A_A") (pintype "passive"))
      (node (ref "JP6") (pin "4") (pinfunction "4_4") (pintype "passive"))
      (node (ref "LED99") (pin "K") (pinfunction "C_K") (pintype "passive"))
      (node (ref "OK5") (pin "2") (pinfunction "C_2") (pintype "passive"))
      (node (ref "OK5") (pin "3") (pinfunction "EMIT_3") (pintype "passive"))
      (node (ref "OK6") (pin "2") (pinfunction "C_2") (pintype "passive"))
      (node (ref "OK6") (pin "3") (pinfunction "EMIT_3") (pintype "passive"))
      (node (ref "Q5") (pin "S") (pinfunction "S_S") (pintype "passive"))
      (node (ref "Q6") (pin "S") (pinfunction "S_S") (pintype "passive"))
      (node (ref "R19") (pin "1") (pinfunction "1_1") (pintype "passive"))
      (node (ref "R20") (pin "1") (pinfunction "1_1") (pintype "passive"))
    )
    (net (code "168") (name "Net-(LED99-PadA)") (class "Default")
      (node (ref "LED99") (pin "A") (pinfunction "A_A") (pintype "passive"))
      (node (ref "R21") (pin "1") (pinfunction "1_1") (pintype "passive"))
    )
    (net (code "169") (name "Net-(LED100-C)") (class "Default")
      (node (ref "D14") (pin "A") (pinfunction "A_A") (pintype "passive"))
      (node (ref "D16") (pin "A") (pinfunction "A_A") (pintype "passive"))
      (node (ref "JP7") (pin "4") (pinfunction "4_4") (pintype "passive"))
      (node (ref "LED100") (pin "K") (pinfunction "C_K") (pintype "passive"))
      (node (ref "OK7") (pin "2") (pinfunction "C_2") (pintype "passive"))
      (node (ref "OK7") (pin "3") (pinfunction "EMIT_3") (pintype "passive"))
      (node (ref "OK8") (pin "2") (pinfunction "C_2") (pintype "passive"))
      (node (ref "OK8") (pin "3") (pinfunction "EMIT_3") (pintype "passive"))
      (node (ref "Q10") (pin "S") (pinfunction "S_S") (pintype "passive"))
      (node (ref "Q9") (pin "S") (pinfunction "S_S") (pintype "passive"))
      (node (ref "R26") (pin "1") (pinfunction "1_1") (pintype "passive"))
      (node (ref "R27") (pin "1") (pinfunction "1_1") (pintype "passive"))
    )
    (net (code "170") (name "Net-(LED100-PadA)") (class "Default")
      (node (ref "LED100") (pin "A") (pinfunction "A_A") (pintype "passive"))
      (node (ref "R28") (pin "1") (pinfunction "1_1") (pintype "passive"))
    )
    (net (code "171") (name "Net-(LED101-C)") (class "Default")
      (node (ref "LED101") (pin "K") (pinfunction "C_K") (pintype "passive"))
      (node (ref "LED102") (pin "K") (pinfunction "C_K") (pintype "passive"))
      (node (ref "LED103") (pin "K") (pinfunction "C_K") (pintype "passive"))
      (node (ref "LED104") (pin "K") (pinfunction "C_K") (pintype "passive"))
      (node (ref "LED105") (pin "K") (pinfunction "C_K") (pintype "passive"))
      (node (ref "LED106") (pin "K") (pinfunction "C_K") (pintype "passive"))
      (node (ref "LED113") (pin "K") (pinfunction "C_K") (pintype "passive"))
      (node (ref "LED114") (pin "K") (pinfunction "C_K") (pintype "passive"))
      (node (ref "LED115") (pin "K") (pinfunction "C_K") (pintype "passive"))
      (node (ref "LED116") (pin "K") (pinfunction "C_K") (pintype "passive"))
      (node (ref "LED117") (pin "K") (pinfunction "C_K") (pintype "passive"))
      (node (ref "LED118") (pin "K") (pinfunction "C_K") (pintype "passive"))
      (node (ref "Q15") (pin "C") (pinfunction "C_C") (pintype "passive"))
    )
    (net (code "172") (name "Net-(LED101-PadA)") (class "Default")
      (node (ref "LED101") (pin "A") (pinfunction "A_A") (pintype "passive"))
      (node (ref "LED102") (pin "A") (pinfunction "A_A") (pintype "passive"))
      (node (ref "LED103") (pin "A") (pinfunction "A_A") (pintype "passive"))
      (node (ref "LED104") (pin "A") (pinfunction "A_A") (pintype "passive"))
      (node (ref "LED105") (pin "A") (pinfunction "A_A") (pintype "passive"))
      (node (ref "LED106") (pin "A") (pinfunction "A_A") (pintype "passive"))
      (node (ref "R29") (pin "1") (pinfunction "1_1") (pintype "passive"))
    )
    (net (code "173") (name "Net-(LED107-C)") (class "Default")
      (node (ref "LED107") (pin "K") (pinfunction "C_K") (pintype "passive"))
      (node (ref "LED108") (pin "K") (pinfunction "C_K") (pintype "passive"))
      (node (ref "LED109") (pin "K") (pinfunction "C_K") (pintype "passive"))
      (node (ref "LED110") (pin "K") (pinfunction "C_K") (pintype "passive"))
      (node (ref "LED111") (pin "K") (pinfunction "C_K") (pintype "passive"))
      (node (ref "LED112") (pin "K") (pinfunction "C_K") (pintype "passive"))
      (node (ref "LED119") (pin "K") (pinfunction "C_K") (pintype "passive"))
      (node (ref "LED120") (pin "K") (pinfunction "C_K") (pintype "passive"))
      (node (ref "LED121") (pin "K") (pinfunction "C_K") (pintype "passive"))
      (node (ref "LED122") (pin "K") (pinfunction "C_K") (pintype "passive"))
      (node (ref "LED123") (pin "K") (pinfunction "C_K") (pintype "passive"))
      (node (ref "LED124") (pin "K") (pinfunction "C_K") (pintype "passive"))
      (node (ref "Q16") (pin "C") (pinfunction "C_C") (pintype "passive"))
    )
    (net (code "174") (name "Net-(LED107-PadA)") (class "Default")
      (node (ref "LED107") (pin "A") (pinfunction "A_A") (pintype "passive"))
      (node (ref "LED108") (pin "A") (pinfunction "A_A") (pintype "passive"))
      (node (ref "LED109") (pin "A") (pinfunction "A_A") (pintype "passive"))
      (node (ref "LED110") (pin "A") (pinfunction "A_A") (pintype "passive"))
      (node (ref "LED111") (pin "A") (pinfunction "A_A") (pintype "passive"))
      (node (ref "LED112") (pin "A") (pinfunction "A_A") (pintype "passive"))
      (node (ref "R30") (pin "1") (pinfunction "1_1") (pintype "passive"))
    )
    (net (code "175") (name "Net-(LED125-C)") (class "Default")
      (node (ref "LED125") (pin "K") (pinfunction "C_K") (pintype "passive"))
      (node (ref "LED126") (pin "K") (pinfunction "C_K") (pintype "passive"))
      (node (ref "LED127") (pin "K") (pinfunction "C_K") (pintype "passive"))
      (node (ref "LED128") (pin "K") (pinfunction "C_K") (pintype "passive"))
      (node (ref "LED129") (pin "K") (pinfunction "C_K") (pintype "passive"))
      (node (ref "LED130") (pin "K") (pinfunction "C_K") (pintype "passive"))
      (node (ref "LED137") (pin "K") (pinfunction "C_K") (pintype "passive"))
      (node (ref "LED138") (pin "K") (pinfunction "C_K") (pintype "passive"))
      (node (ref "LED139") (pin "K") (pinfunction "C_K") (pintype "passive"))
      (node (ref "LED140") (pin "K") (pinfunction "C_K") (pintype "passive"))
      (node (ref "LED141") (pin "K") (pinfunction "C_K") (pintype "passive"))
      (node (ref "LED142") (pin "K") (pinfunction "C_K") (pintype "passive"))
      (node (ref "Q19") (pin "C") (pinfunction "C_C") (pintype "passive"))
    )
    (net (code "176") (name "Net-(LED125-PadA)") (class "Default")
      (node (ref "LED125") (pin "A") (pinfunction "A_A") (pintype "passive"))
      (node (ref "LED126") (pin "A") (pinfunction "A_A") (pintype "passive"))
      (node (ref "LED127") (pin "A") (pinfunction "A_A") (pintype "passive"))
      (node (ref "LED128") (pin "A") (pinfunction "A_A") (pintype "passive"))
      (node (ref "LED129") (pin "A") (pinfunction "A_A") (pintype "passive"))
      (node (ref "LED130") (pin "A") (pinfunction "A_A") (pintype "passive"))
      (node (ref "R33") (pin "1") (pinfunction "1_1") (pintype "passive"))
    )
    (net (code "177") (name "Net-(LED131-C)") (class "Default")
      (node (ref "LED131") (pin "K") (pinfunction "C_K") (pintype "passive"))
      (node (ref "LED132") (pin "K") (pinfunction "C_K") (pintype "passive"))
      (node (ref "LED133") (pin "K") (pinfunction "C_K") (pintype "passive"))
      (node (ref "LED134") (pin "K") (pinfunction "C_K") (pintype "passive"))
      (node (ref "LED135") (pin "K") (pinfunction "C_K") (pintype "passive"))
      (node (ref "LED136") (pin "K") (pinfunction "C_K") (pintype "passive"))
      (node (ref "LED143") (pin "K") (pinfunction "C_K") (pintype "passive"))
      (node (ref "LED144") (pin "K") (pinfunction "C_K") (pintype "passive"))
      (node (ref "LED145") (pin "K") (pinfunction "C_K") (pintype "passive"))
      (node (ref "LED146") (pin "K") (pinfunction "C_K") (pintype "passive"))
      (node (ref "LED147") (pin "K") (pinfunction "C_K") (pintype "passive"))
      (node (ref "LED148") (pin "K") (pinfunction "C_K") (pintype "passive"))
      (node (ref "Q20") (pin "C") (pinfunction "C_C") (pintype "passive"))
    )
    (net (code "178") (name "Net-(LED131-PadA)") (class "Default")
      (node (ref "LED131") (pin "A") (pinfunction "A_A") (pintype "passive"))
      (node (ref "LED132") (pin "A") (pinfunction "A_A") (pintype "passive"))
      (node (ref "LED133") (pin "A") (pinfunction "A_A") (pintype "passive"))
      (node (ref "LED134") (pin "A") (pinfunction "A_A") (pintype "passive"))
      (node (ref "LED135") (pin "A") (pinfunction "A_A") (pintype "passive"))
      (node (ref "LED136") (pin "A") (pinfunction "A_A") (pintype "passive"))
      (node (ref "R34") (pin "1") (pinfunction "1_1") (pintype "passive"))
    )
    (net (code "179") (name "Net-(OK1-A)") (class "Default")
      (node (ref "OK1") (pin "1") (pinfunction "A_1") (pintype "passive"))
      (node (ref "R1") (pin "2") (pinfunction "2_2") (pintype "passive"))
    )
    (net (code "180") (name "Net-(OK1-COL)") (class "Default")
      (node (ref "OK1") (pin "4") (pinfunction "COL_4") (pintype "passive"))
      (node (ref "Q13") (pin "G") (pinfunction "G_G") (pintype "passive"))
      (node (ref "Q17") (pin "G") (pinfunction "G_G") (pintype "passive"))
      (node (ref "R6") (pin "1") (pinfunction "1_1") (pintype "passive"))
      (node (ref "R7") (pin "2") (pinfunction "2_2") (pintype "passive"))
    )
    (net (code "181") (name "Net-(OK2-A)") (class "Default")
      (node (ref "OK2") (pin "1") (pinfunction "A_1") (pintype "passive"))
      (node (ref "R4") (pin "1") (pinfunction "1_1") (pintype "passive"))
    )
    (net (code "182") (name "Net-(OK2-COL)") (class "Default")
      (node (ref "OK2") (pin "4") (pinfunction "COL_4") (pintype "passive"))
      (node (ref "Q14") (pin "G") (pinfunction "G_G") (pintype "passive"))
      (node (ref "Q18") (pin "G") (pinfunction "G_G") (pintype "passive"))
      (node (ref "R3") (pin "2") (pinfunction "2_2") (pintype "passive"))
      (node (ref "R5") (pin "1") (pinfunction "1_1") (pintype "passive"))
    )
    (net (code "183") (name "Net-(OK3-A)") (class "Default")
      (node (ref "OK3") (pin "1") (pinfunction "A_1") (pintype "passive"))
      (node (ref "R2") (pin "2") (pinfunction "2_2") (pintype "passive"))
    )
    (net (code "184") (name "Net-(OK3-COL)") (class "Default")
      (node (ref "OK3") (pin "4") (pinfunction "COL_4") (pintype "passive"))
      (node (ref "Q1") (pin "G") (pinfunction "G_G") (pintype "passive"))
      (node (ref "Q3") (pin "G") (pinfunction "G_G") (pintype "passive"))
      (node (ref "R11") (pin "1") (pinfunction "1_1") (pintype "passive"))
      (node (ref "R13") (pin "2") (pinfunction "2_2") (pintype "passive"))
    )
    (net (code "185") (name "Net-(OK4-A)") (class "Default")
      (node (ref "OK4") (pin "1") (pinfunction "A_1") (pintype "passive"))
      (node (ref "R9") (pin "1") (pinfunction "1_1") (pintype "passive"))
    )
    (net (code "186") (name "Net-(OK4-COL)") (class "Default")
      (node (ref "OK4") (pin "4") (pinfunction "COL_4") (pintype "passive"))
      (node (ref "Q2") (pin "G") (pinfunction "G_G") (pintype "passive"))
      (node (ref "Q4") (pin "G") (pinfunction "G_G") (pintype "passive"))
      (node (ref "R10") (pin "1") (pinfunction "1_1") (pintype "passive"))
      (node (ref "R12") (pin "2") (pinfunction "2_2") (pintype "passive"))
    )
    (net (code "187") (name "Net-(OK5-A)") (class "Default")
      (node (ref "OK5") (pin "1") (pinfunction "A_1") (pintype "passive"))
      (node (ref "R15") (pin "2") (pinfunction "2_2") (pintype "passive"))
    )
    (net (code "188") (name "Net-(OK5-COL)") (class "Default")
      (node (ref "OK5") (pin "4") (pinfunction "COL_4") (pintype "passive"))
      (node (ref "Q5") (pin "G") (pinfunction "G_G") (pintype "passive"))
      (node (ref "Q7") (pin "G") (pinfunction "G_G") (pintype "passive"))
      (node (ref "R18") (pin "1") (pinfunction "1_1") (pintype "passive"))
      (node (ref "R20") (pin "2") (pinfunction "2_2") (pintype "passive"))
    )
    (net (code "189") (name "Net-(OK6-A)") (class "Default")
      (node (ref "OK6") (pin "1") (pinfunction "A_1") (pintype "passive"))
      (node (ref "R16") (pin "1") (pinfunction "1_1") (pintype "passive"))
    )
    (net (code "190") (name "Net-(OK6-COL)") (class "Default")
      (node (ref "OK6") (pin "4") (pinfunction "COL_4") (pintype "passive"))
      (node (ref "Q6") (pin "G") (pinfunction "G_G") (pintype "passive"))
      (node (ref "Q8") (pin "G") (pinfunction "G_G") (pintype "passive"))
      (node (ref "R17") (pin "1") (pinfunction "1_1") (pintype "passive"))
      (node (ref "R19") (pin "2") (pinfunction "2_2") (pintype "passive"))
    )
    (net (code "191") (name "Net-(OK7-A)") (class "Default")
      (node (ref "OK7") (pin "1") (pinfunction "A_1") (pintype "passive"))
      (node (ref "R22") (pin "2") (pinfunction "2_2") (pintype "passive"))
    )
    (net (code "192") (name "Net-(OK7-COL)") (class "Default")
      (node (ref "OK7") (pin "4") (pinfunction "COL_4") (pintype "passive"))
      (node (ref "Q11") (pin "G") (pinfunction "G_G") (pintype "passive"))
      (node (ref "Q9") (pin "G") (pinfunction "G_G") (pintype "passive"))
      (node (ref "R25") (pin "1") (pinfunction "1_1") (pintype "passive"))
      (node (ref "R27") (pin "2") (pinfunction "2_2") (pintype "passive"))
    )
    (net (code "193") (name "Net-(OK8-A)") (class "Default")
      (node (ref "OK8") (pin "1") (pinfunction "A_1") (pintype "passive"))
      (node (ref "R23") (pin "1") (pinfunction "1_1") (pintype "passive"))
    )
    (net (code "194") (name "Net-(OK8-COL)") (class "Default")
      (node (ref "OK8") (pin "4") (pinfunction "COL_4") (pintype "passive"))
      (node (ref "Q10") (pin "G") (pinfunction "G_G") (pintype "passive"))
      (node (ref "Q12") (pin "G") (pinfunction "G_G") (pintype "passive"))
      (node (ref "R24") (pin "1") (pinfunction "1_1") (pintype "passive"))
      (node (ref "R26") (pin "2") (pinfunction "2_2") (pintype "passive"))
    )
    (net (code "195") (name "Net-(Q15-PadB)") (class "Default")
      (node (ref "Q15") (pin "B") (pinfunction "B_B") (pintype "passive"))
      (node (ref "R32") (pin "1") (pinfunction "1_1") (pintype "passive"))
    )
    (net (code "196") (name "Net-(Q16-PadB)") (class "Default")
      (node (ref "Q16") (pin "B") (pinfunction "B_B") (pintype "passive"))
      (node (ref "R31") (pin "1") (pinfunction "1_1") (pintype "passive"))
    )
    (net (code "197") (name "Net-(Q19-PadB)") (class "Default")
      (node (ref "Q19") (pin "B") (pinfunction "B_B") (pintype "passive"))
      (node (ref "R35") (pin "1") (pinfunction "1_1") (pintype "passive"))
    )
    (net (code "198") (name "Net-(Q20-PadB)") (class "Default")
      (node (ref "Q20") (pin "B") (pinfunction "B_B") (pintype "passive"))
      (node (ref "R36") (pin "1") (pinfunction "1_1") (pintype "passive"))
    )
    (net (code "199") (name "unconnected-(RN13-Pad2)") (class "Default")
      (node (ref "RN13") (pin "2") (pinfunction "2_2") (pintype "passive"))
    )
    (net (code "200") (name "unconnected-(RN13-Pad3)") (class "Default")
      (node (ref "RN13") (pin "3") (pinfunction "3_3") (pintype "passive"))
    )
    (net (code "201") (name "unconnected-(RN14-Pad8)") (class "Default")
      (node (ref "RN14") (pin "8") (pinfunction "8_8") (pintype "passive"))
    )
    (net (code "202") (name "unconnected-(RN14-Pad9)") (class "Default")
      (node (ref "RN14") (pin "9") (pinfunction "9_9") (pintype "passive"))
    )
    (net (code "203") (name "unconnected-(SV1-Pad2)") (class "Default")
      (node (ref "SV1") (pin "2") (pinfunction "2_2") (pintype "passive"))
    )
    (net (code "204") (name "unconnected-(SV2-Pad2)") (class "Default")
      (node (ref "SV2") (pin "2") (pinfunction "2_2") (pintype "passive"))
    )
    (net (code "205") (name "unconnected-(SV3-Pad2)") (class "Default")
      (node (ref "SV3") (pin "2") (pinfunction "2_2") (pintype "passive"))
    )
    (net (code "206") (name "unconnected-(SV4-Pad2)") (class "Default")
      (node (ref "SV4") (pin "2") (pinfunction "2_2") (pintype "passive"))
    )
  )
)
